# GEM_HV_channel.net
KiCad netlist of a schematic drawn in Altium Designer
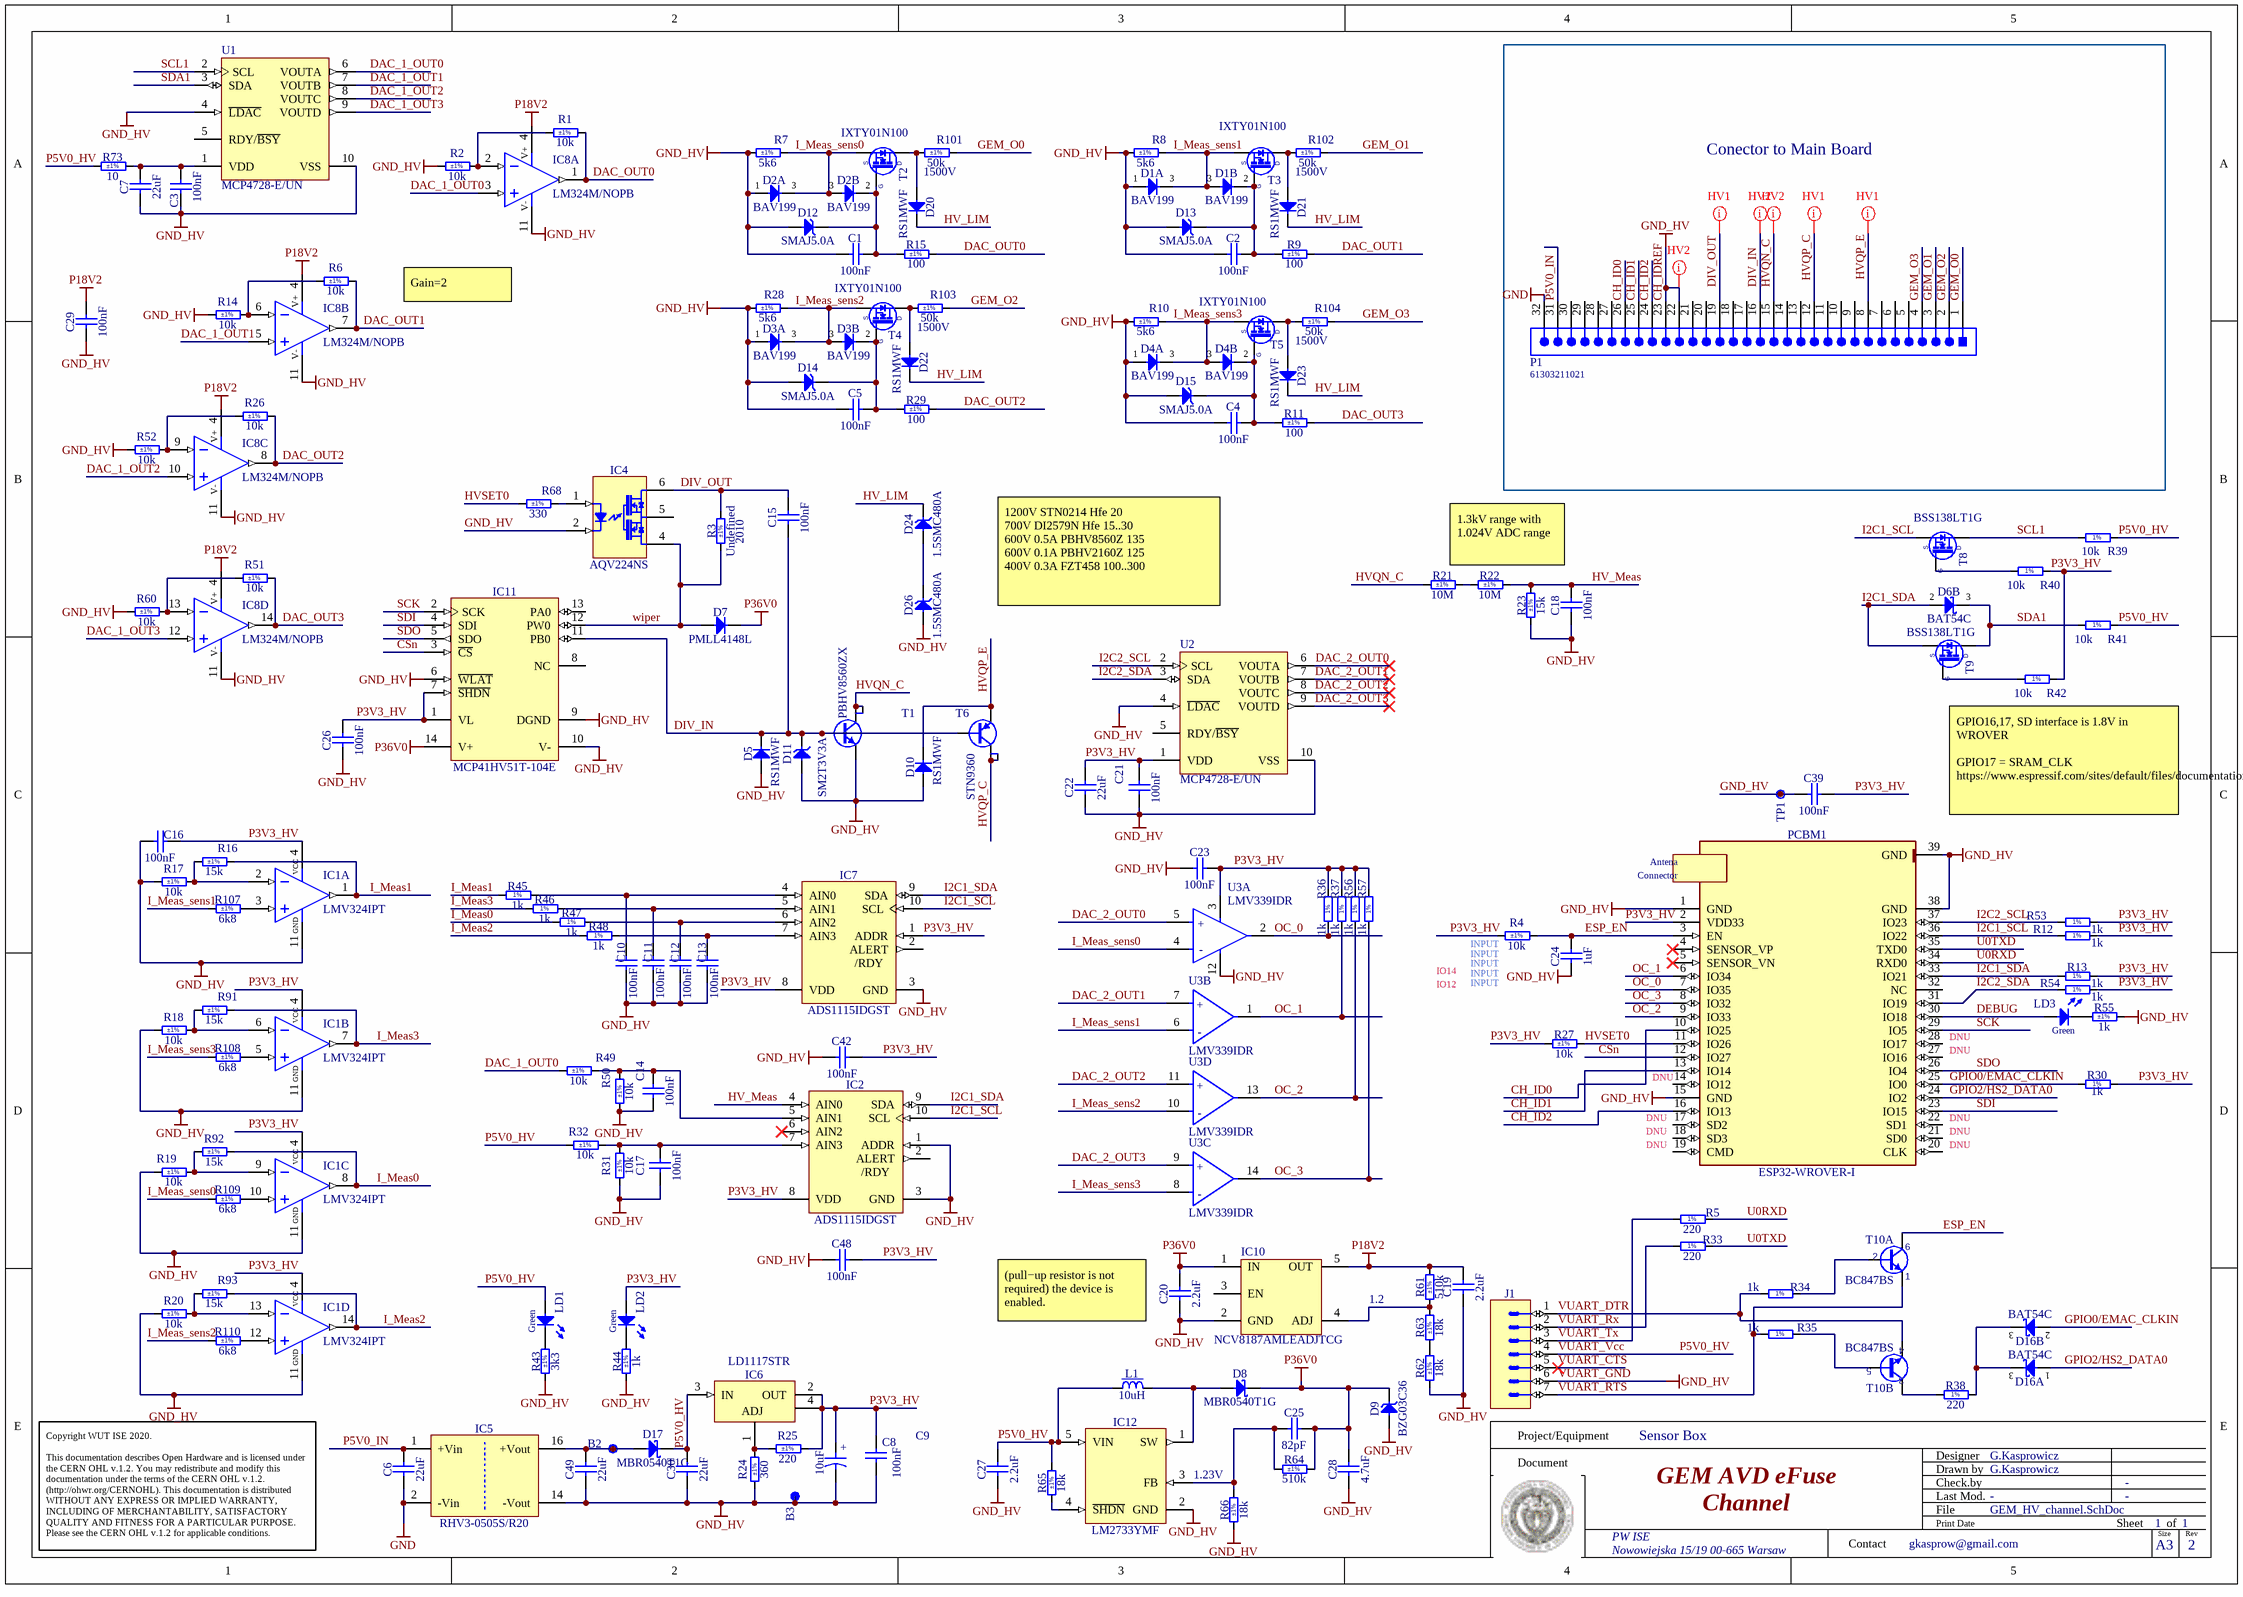
[diagram p0: GEM_HV_channel.SchDoc]

(export (version "E")
  (design (tool "Eeschema 10.0.6"))
  (components
    (comp (ref "B2")
      (value "SMD Pad")
      (footprint "C100")
      (description "Pad")
      (fields (field (name "PART NUMBER") "SMD_PAD_D1MM") (field (name "AUTHOR") "CERN DEM JLC"))
      (libsource (lib "Eletro-mechanical") (part "Single SMD Pad (Round)"))
    )
    (comp (ref "B3")
      (value "SMD Pad")
      (footprint "C100")
      (description "Pad")
      (fields (field (name "PART NUMBER") "SMD_PAD_D1MM") (field (name "AUTHOR") "CERN DEM JLC"))
      (libsource (lib "Eletro-mechanical") (part "Single SMD Pad (Round)"))
    )
    (comp (ref "C1")
      (value "100nF")
      (footprint "CAPC1608X87N")
      (description "Non-polarised capacitor")
      (fields
        (field (name "PART NUMBER") "CC0603_100NF_50V_10%_X5R")
        (field (name "VOLTAGE") "50V")
        (field (name "AUTHOR") "CERN DEM MR")
      )
      (libsource (lib "Capacitors") (part "Capacitor - non polarized"))
    )
    (comp (ref "C2")
      (value "100nF")
      (footprint "CAPC1608X87N")
      (description "Non-polarised capacitor")
      (fields
        (field (name "PART NUMBER") "CC0603_100NF_50V_10%_X5R")
        (field (name "VOLTAGE") "50V")
        (field (name "AUTHOR") "CERN DEM MR")
      )
      (libsource (lib "Capacitors") (part "Capacitor - non polarized"))
    )
    (comp (ref "C3")
      (value "100nF")
      (footprint "CAPC1608X87N")
      (description "Non-polarised capacitor")
      (fields
        (field (name "PART NUMBER") "CC0603_100NF_50V_10%_X5R")
        (field (name "VOLTAGE") "50V")
        (field (name "AUTHOR") "CERN DEM MR")
      )
      (libsource (lib "Capacitors") (part "Capacitor - non polarized"))
    )
    (comp (ref "C4")
      (value "100nF")
      (footprint "CAPC1608X87N")
      (description "Non-polarised capacitor")
      (fields
        (field (name "PART NUMBER") "CC0603_100NF_50V_10%_X5R")
        (field (name "VOLTAGE") "50V")
        (field (name "AUTHOR") "CERN DEM MR")
      )
      (libsource (lib "Capacitors") (part "Capacitor - non polarized"))
    )
    (comp (ref "C5")
      (value "100nF")
      (footprint "CAPC1608X87N")
      (description "Non-polarised capacitor")
      (fields
        (field (name "PART NUMBER") "CC0603_100NF_50V_10%_X5R")
        (field (name "VOLTAGE") "50V")
        (field (name "AUTHOR") "CERN DEM MR")
      )
      (libsource (lib "Capacitors") (part "Capacitor - non polarized"))
    )
    (comp (ref "C6")
      (value "22uF")
      (footprint "CAPC2012X145N")
      (description "Non-polarised capacitor")
      (fields
        (field (name "PART NUMBER") "CC0805_22UF_25V_20%_X5R")
        (field (name "VOLTAGE") "25V")
        (field (name "AUTHOR") "CERN DEM WB")
      )
      (libsource (lib "Capacitors") (part "Capacitor - non polarized"))
    )
    (comp (ref "C7")
      (value "22uF")
      (footprint "CAPC2012X145N")
      (description "Non-polarised capacitor")
      (fields
        (field (name "PART NUMBER") "CC0805_22UF_25V_20%_X5R")
        (field (name "VOLTAGE") "25V")
        (field (name "AUTHOR") "CERN DEM WB")
      )
      (libsource (lib "Capacitors") (part "Capacitor - non polarized"))
    )
    (comp (ref "C8")
      (value "10uF")
      (footprint "CAPAE430X540N")
      (description "Polarised capacitor")
      (fields
        (field (name "PART NUMBER") "CAE430-540_10UF_16V_20%")
        (field (name "VOLTAGE") "16V")
        (field (name "AUTHOR") "CERN DEM JLC")
      )
      (libsource (lib "Capacitors") (part "Capacitor - polarized"))
    )
    (comp (ref "C9")
      (value "100nF")
      (footprint "CAPC1608X87N")
      (description "Non-polarised capacitor")
      (fields
        (field (name "PART NUMBER") "CC0603_100NF_50V_10%_X5R")
        (field (name "VOLTAGE") "50V")
        (field (name "AUTHOR") "CERN DEM MR")
      )
      (libsource (lib "Capacitors") (part "Capacitor - non polarized"))
    )
    (comp (ref "C10")
      (value "100nF")
      (footprint "CAPC1608X87N")
      (description "Non-polarised capacitor")
      (fields
        (field (name "PART NUMBER") "CC0603_100NF_50V_10%_X5R")
        (field (name "VOLTAGE") "50V")
        (field (name "AUTHOR") "CERN DEM MR")
      )
      (libsource (lib "Capacitors") (part "Capacitor - non polarized"))
    )
    (comp (ref "C11")
      (value "100nF")
      (footprint "CAPC1608X87N")
      (description "Non-polarised capacitor")
      (fields
        (field (name "PART NUMBER") "CC0603_100NF_50V_10%_X5R")
        (field (name "VOLTAGE") "50V")
        (field (name "AUTHOR") "CERN DEM MR")
      )
      (libsource (lib "Capacitors") (part "Capacitor - non polarized"))
    )
    (comp (ref "C12")
      (value "100nF")
      (footprint "CAPC1608X87N")
      (description "Non-polarised capacitor")
      (fields
        (field (name "PART NUMBER") "CC0603_100NF_50V_10%_X5R")
        (field (name "VOLTAGE") "50V")
        (field (name "AUTHOR") "CERN DEM MR")
      )
      (libsource (lib "Capacitors") (part "Capacitor - non polarized"))
    )
    (comp (ref "C13")
      (value "100nF")
      (footprint "CAPC1608X87N")
      (description "Non-polarised capacitor")
      (fields
        (field (name "PART NUMBER") "CC0603_100NF_50V_10%_X5R")
        (field (name "VOLTAGE") "50V")
        (field (name "AUTHOR") "CERN DEM MR")
      )
      (libsource (lib "Capacitors") (part "Capacitor - non polarized"))
    )
    (comp (ref "C14")
      (value "100nF")
      (footprint "CAPC1608X87N")
      (description "Non-polarised capacitor")
      (fields
        (field (name "PART NUMBER") "CC0603_100NF_50V_10%_X5R")
        (field (name "VOLTAGE") "50V")
        (field (name "AUTHOR") "CERN DEM MR")
      )
      (libsource (lib "Capacitors") (part "Capacitor - non polarized"))
    )
    (comp (ref "C15")
      (value "100nF")
      (footprint "CAPC4532X185N")
      (description "Non-polarised capacitor")
      (fields
        (field (name "PART NUMBER") "CC1812_100NF_1000V_10%_X7R_KEMET_HV FT-CAP")
        (field (name "VOLTAGE") "1000V")
        (field (name "AUTHOR") "CERN DEM MR")
      )
      (libsource (lib "Capacitors") (part "Capacitor - non polarized"))
    )
    (comp (ref "C16")
      (value "100nF")
      (footprint "CAPC1608X87N")
      (description "Non-polarised capacitor")
      (fields
        (field (name "PART NUMBER") "CC0603_100NF_50V_10%_X5R")
        (field (name "VOLTAGE") "50V")
        (field (name "AUTHOR") "CERN DEM MR")
      )
      (libsource (lib "Capacitors") (part "Capacitor - non polarized"))
    )
    (comp (ref "C17")
      (value "100nF")
      (footprint "CAPC1608X87N")
      (description "Non-polarised capacitor")
      (fields
        (field (name "PART NUMBER") "CC0603_100NF_50V_10%_X5R")
        (field (name "VOLTAGE") "50V")
        (field (name "AUTHOR") "CERN DEM MR")
      )
      (libsource (lib "Capacitors") (part "Capacitor - non polarized"))
    )
    (comp (ref "C18")
      (value "100nF")
      (footprint "CAPC1608X87N")
      (description "Non-polarised capacitor")
      (fields
        (field (name "PART NUMBER") "CC0603_100NF_50V_10%_X5R")
        (field (name "VOLTAGE") "50V")
        (field (name "AUTHOR") "CERN DEM MR")
      )
      (libsource (lib "Capacitors") (part "Capacitor - non polarized"))
    )
    (comp (ref "C19")
      (value "2.2uF")
      (footprint "CAPC1608X87N")
      (description "Non-polarised capacitor")
      (fields
        (field (name "PART NUMBER") "CC0603_2.2UF_16V_10%_X5R")
        (field (name "VOLTAGE") "16V")
        (field (name "AUTHOR") "CERN DEM JLC")
      )
      (libsource (lib "Capacitors") (part "Capacitor - non polarized"))
    )
    (comp (ref "C20")
      (value "2.2uF")
      (footprint "CAPC1608X87N")
      (description "Non-polarised capacitor")
      (fields
        (field (name "PART NUMBER") "CC0603_2.2UF_16V_10%_X5R")
        (field (name "VOLTAGE") "16V")
        (field (name "AUTHOR") "CERN DEM JLC")
      )
      (libsource (lib "Capacitors") (part "Capacitor - non polarized"))
    )
    (comp (ref "C21")
      (value "100nF")
      (footprint "CAPC1608X87N")
      (description "Non-polarised capacitor")
      (fields
        (field (name "PART NUMBER") "CC0603_100NF_50V_10%_X5R")
        (field (name "VOLTAGE") "50V")
        (field (name "AUTHOR") "CERN DEM MR")
      )
      (libsource (lib "Capacitors") (part "Capacitor - non polarized"))
    )
    (comp (ref "C22")
      (value "22uF")
      (footprint "CAPC2012X145N")
      (description "Non-polarised capacitor")
      (fields
        (field (name "PART NUMBER") "CC0805_22UF_25V_20%_X5R")
        (field (name "VOLTAGE") "25V")
        (field (name "AUTHOR") "CERN DEM WB")
      )
      (libsource (lib "Capacitors") (part "Capacitor - non polarized"))
    )
    (comp (ref "C23")
      (value "100nF")
      (footprint "CAPC1608X87N")
      (description "Non-polarised capacitor")
      (fields
        (field (name "PART NUMBER") "CC0603_100NF_50V_10%_X5R")
        (field (name "VOLTAGE") "50V")
        (field (name "AUTHOR") "CERN DEM MR")
      )
      (libsource (lib "Capacitors") (part "Capacitor - non polarized"))
    )
    (comp (ref "C24")
      (value "1uF")
      (footprint "CAPC1608X87N")
      (description "Non-polarised capacitor")
      (fields
        (field (name "PART NUMBER") "CC0603_1UF_25V_10%_X7R")
        (field (name "VOLTAGE") "25V")
        (field (name "AUTHOR") "CERN DEM JLC")
      )
      (libsource (lib "Capacitors") (part "Capacitor - non polarized"))
    )
    (comp (ref "C25")
      (value "82pF")
      (footprint "CAPC1608X87N")
      (description "Non-polarised capacitor")
      (fields
        (field (name "PART NUMBER") "CC0603_82PF_50V_5%_NP0")
        (field (name "VOLTAGE") "50V")
        (field (name "AUTHOR") "CERN DEM JLC")
      )
      (libsource (lib "Capacitors") (part "Capacitor - non polarized"))
    )
    (comp (ref "C26")
      (value "100nF")
      (footprint "CAPC1608X87N")
      (description "Non-polarised capacitor")
      (fields
        (field (name "PART NUMBER") "CC0603_100NF_50V_10%_X5R")
        (field (name "VOLTAGE") "50V")
        (field (name "AUTHOR") "CERN DEM MR")
      )
      (libsource (lib "Capacitors") (part "Capacitor - non polarized"))
    )
    (comp (ref "C27")
      (value "2.2uF")
      (footprint "CAPC1608X87N")
      (description "Non-polarised capacitor")
      (fields
        (field (name "PART NUMBER") "CC0603_2.2UF_16V_10%_X5R")
        (field (name "VOLTAGE") "16V")
        (field (name "AUTHOR") "CERN DEM JLC")
      )
      (libsource (lib "Capacitors") (part "Capacitor - non polarized"))
    )
    (comp (ref "C28")
      (value "4.7uF")
      (footprint "CAPC3225X270N")
      (description "Non-polarised capacitor")
      (fields
        (field (name "PART NUMBER") "CC1210_4.7UF_50V_10%_X7R")
        (field (name "VOLTAGE") "50V")
        (field (name "AUTHOR") "CERN DEM JLC")
      )
      (libsource (lib "Capacitors") (part "Capacitor - non polarized"))
    )
    (comp (ref "C29")
      (value "100nF")
      (footprint "CAPC1608X87N")
      (description "Non-polarised capacitor")
      (fields
        (field (name "PART NUMBER") "CC0603_100NF_50V_10%_X5R")
        (field (name "VOLTAGE") "50V")
        (field (name "AUTHOR") "CERN DEM MR")
      )
      (libsource (lib "Capacitors") (part "Capacitor - non polarized"))
    )
    (comp (ref "C30")
      (value "22uF")
      (footprint "CAPC2012X145N")
      (description "Non-polarised capacitor")
      (fields
        (field (name "PART NUMBER") "CC0805_22UF_25V_20%_X5R")
        (field (name "VOLTAGE") "25V")
        (field (name "AUTHOR") "CERN DEM WB")
      )
      (libsource (lib "Capacitors") (part "Capacitor - non polarized"))
    )
    (comp (ref "C39")
      (value "100nF")
      (footprint "CAPC1608X87N")
      (description "Non-polarised capacitor")
      (fields
        (field (name "PART NUMBER") "CC0603_100NF_50V_10%_X5R")
        (field (name "VOLTAGE") "50V")
        (field (name "AUTHOR") "CERN DEM MR")
      )
      (libsource (lib "Capacitors") (part "Capacitor - non polarized"))
    )
    (comp (ref "C42")
      (value "100nF")
      (footprint "CAPC1608X87N")
      (description "Non-polarised capacitor")
      (fields
        (field (name "PART NUMBER") "CC0603_100NF_50V_10%_X5R")
        (field (name "VOLTAGE") "50V")
        (field (name "AUTHOR") "CERN DEM MR")
      )
      (libsource (lib "Capacitors") (part "Capacitor - non polarized"))
    )
    (comp (ref "C48")
      (value "100nF")
      (footprint "CAPC1608X87N")
      (description "Non-polarised capacitor")
      (fields
        (field (name "PART NUMBER") "CC0603_100NF_50V_10%_X5R")
        (field (name "VOLTAGE") "50V")
        (field (name "AUTHOR") "CERN DEM MR")
      )
      (libsource (lib "Capacitors") (part "Capacitor - non polarized"))
    )
    (comp (ref "C49")
      (value "22uF")
      (footprint "CAPC2012X145N")
      (description "Non-polarised capacitor")
      (fields
        (field (name "PART NUMBER") "CC0805_22UF_25V_20%_X5R")
        (field (name "VOLTAGE") "25V")
        (field (name "AUTHOR") "CERN DEM WB")
      )
      (libsource (lib "Capacitors") (part "Capacitor - non polarized"))
    )
    (comp (ref "D1")
      (value "BAV199")
      (footprint "SOT95P240X110-3N")
      (description "Serial Diode")
      (fields
        (field (name "VOLTAGE") "75V")
        (field (name "POWER") "250mW")
        (field (name "AUTHOR") "CERN DEM JMW")
      )
      (libsource (lib "ICs And Semiconductors") (part "Diode x2 A1C3_A3C2"))
    )
    (comp (ref "D2")
      (value "BAV199")
      (footprint "SOT95P240X110-3N")
      (description "Serial Diode")
      (fields
        (field (name "VOLTAGE") "75V")
        (field (name "POWER") "250mW")
        (field (name "AUTHOR") "CERN DEM JMW")
      )
      (libsource (lib "ICs And Semiconductors") (part "Diode x2 A1C3_A3C2"))
    )
    (comp (ref "D3")
      (value "BAV199")
      (footprint "SOT95P240X110-3N")
      (description "Serial Diode")
      (fields
        (field (name "VOLTAGE") "75V")
        (field (name "POWER") "250mW")
        (field (name "AUTHOR") "CERN DEM JMW")
      )
      (libsource (lib "ICs And Semiconductors") (part "Diode x2 A1C3_A3C2"))
    )
    (comp (ref "D4")
      (value "BAV199")
      (footprint "SOT95P240X110-3N")
      (description "Serial Diode")
      (fields
        (field (name "VOLTAGE") "75V")
        (field (name "POWER") "250mW")
        (field (name "AUTHOR") "CERN DEM JMW")
      )
      (libsource (lib "ICs And Semiconductors") (part "Diode x2 A1C3_A3C2"))
    )
    (comp (ref "D5")
      (value "RS1MWF")
      (footprint "SOD-123F")
      (description "Diode")
      (fields
        (field (name "VOLTAGE") "1000V")
        (field (name "POWER") "1A")
        (field (name "AUTHOR") "CERN DEM HF")
      )
      (libsource (lib "ICs And Semiconductors") (part "Diode"))
    )
    (comp (ref "D6")
      (value "BAT54C")
      (footprint "SOT95P240X130-3N")
      (description "Dual Common Cathode Schottky Diodes")
      (fields
        (field (name "VOLTAGE") "30V")
        (field (name "POWER") "200mA")
        (field (name "AUTHOR") "CERN DEM JLC")
      )
      (libsource (lib "ICs And Semiconductors") (part "Diode Schottky x2 A1C3_A2C3"))
    )
    (comp (ref "D7")
      (value "PMLL4148L")
      (footprint "DIOMELF3515N")
      (description "Diode")
      (fields
        (field (name "VOLTAGE") "75V")
        (field (name "POWER") "200mA")
        (field (name "AUTHOR") "CERN DEM JLC")
      )
      (libsource (lib "ICs And Semiconductors") (part "Diode"))
    )
    (comp (ref "D8")
      (value "MBR0540T1G")
      (footprint "SOD3716X135N")
      (description "Schottky Diode")
      (fields
        (field (name "VOLTAGE") "40V")
        (field (name "POWER") "500mA")
        (field (name "AUTHOR") "CERN DEM JLC")
      )
      (libsource (lib "ICs And Semiconductors") (part "Diode Schottky"))
    )
    (comp (ref "D9")
      (value "BZG03C36")
      (footprint "DIOM5326X230N")
      (description "Zener Diode")
      (fields
        (field (name "VOLTAGE") "36V")
        (field (name "POWER") "1.25W")
        (field (name "AUTHOR") "CERN DEM JLC")
      )
      (libsource (lib "ICs And Semiconductors") (part "Diode Zener"))
    )
    (comp (ref "D10")
      (value "RS1MWF")
      (footprint "SOD-123F")
      (description "Diode")
      (fields
        (field (name "VOLTAGE") "1000V")
        (field (name "POWER") "1A")
        (field (name "AUTHOR") "CERN DEM HF")
      )
      (libsource (lib "ICs And Semiconductors") (part "Diode"))
    )
    (comp (ref "D11")
      (value "SM2T3V3A")
      (footprint "DO-216AA")
      (description "Transient Voltage Suppressor Diode (Uni-Directional)")
      (fields
        (field (name "VOLTAGE") "3V3")
        (field (name "POWER") "200W")
        (field (name "AUTHOR") "CERN DEM BR")
      )
      (libsource (lib "ICs And Semiconductors") (part "Diode TVS Uni-Directional"))
    )
    (comp (ref "D12")
      (value "SMAJ5.0A")
      (footprint "DIOM5226X262N")
      (description "Transient Voltage Suppressor Diode (Uni-Directional)")
      (fields
        (field (name "VOLTAGE") "5V")
        (field (name "POWER") "400W")
        (field (name "AUTHOR") "CERN DEM MR")
      )
      (libsource (lib "ICs And Semiconductors") (part "Diode TVS Uni-Directional"))
    )
    (comp (ref "D13")
      (value "SMAJ5.0A")
      (footprint "DIOM5226X262N")
      (description "Transient Voltage Suppressor Diode (Uni-Directional)")
      (fields
        (field (name "VOLTAGE") "5V")
        (field (name "POWER") "400W")
        (field (name "AUTHOR") "CERN DEM MR")
      )
      (libsource (lib "ICs And Semiconductors") (part "Diode TVS Uni-Directional"))
    )
    (comp (ref "D14")
      (value "SMAJ5.0A")
      (footprint "DIOM5226X262N")
      (description "Transient Voltage Suppressor Diode (Uni-Directional)")
      (fields
        (field (name "VOLTAGE") "5V")
        (field (name "POWER") "400W")
        (field (name "AUTHOR") "CERN DEM MR")
      )
      (libsource (lib "ICs And Semiconductors") (part "Diode TVS Uni-Directional"))
    )
    (comp (ref "D15")
      (value "SMAJ5.0A")
      (footprint "DIOM5226X262N")
      (description "Transient Voltage Suppressor Diode (Uni-Directional)")
      (fields
        (field (name "VOLTAGE") "5V")
        (field (name "POWER") "400W")
        (field (name "AUTHOR") "CERN DEM MR")
      )
      (libsource (lib "ICs And Semiconductors") (part "Diode TVS Uni-Directional"))
    )
    (comp (ref "D16")
      (value "BAT54C")
      (footprint "SOT95P240X130-3N")
      (description "Dual Common Cathode Schottky Diodes")
      (fields
        (field (name "VOLTAGE") "30V")
        (field (name "POWER") "200mA")
        (field (name "AUTHOR") "CERN DEM JLC")
      )
      (libsource (lib "ICs And Semiconductors") (part "Diode Schottky x2 A1C3_A2C3"))
    )
    (comp (ref "D17")
      (value "MBR0540T1G")
      (footprint "SOD3716X135N")
      (description "Schottky Diode")
      (fields
        (field (name "VOLTAGE") "40V")
        (field (name "POWER") "500mA")
        (field (name "AUTHOR") "CERN DEM JLC")
      )
      (libsource (lib "ICs And Semiconductors") (part "Diode Schottky"))
    )
    (comp (ref "D20")
      (value "RS1MWF")
      (footprint "SOD-123F")
      (description "Diode")
      (fields
        (field (name "VOLTAGE") "1000V")
        (field (name "POWER") "1A")
        (field (name "AUTHOR") "CERN DEM HF")
      )
      (libsource (lib "ICs And Semiconductors") (part "Diode"))
    )
    (comp (ref "D21")
      (value "RS1MWF")
      (footprint "SOD-123F")
      (description "Diode")
      (fields
        (field (name "VOLTAGE") "1000V")
        (field (name "POWER") "1A")
        (field (name "AUTHOR") "CERN DEM HF")
      )
      (libsource (lib "ICs And Semiconductors") (part "Diode"))
    )
    (comp (ref "D22")
      (value "RS1MWF")
      (footprint "SOD-123F")
      (description "Diode")
      (fields
        (field (name "VOLTAGE") "1000V")
        (field (name "POWER") "1A")
        (field (name "AUTHOR") "CERN DEM HF")
      )
      (libsource (lib "ICs And Semiconductors") (part "Diode"))
    )
    (comp (ref "D23")
      (value "RS1MWF")
      (footprint "SOD-123F")
      (description "Diode")
      (fields
        (field (name "VOLTAGE") "1000V")
        (field (name "POWER") "1A")
        (field (name "AUTHOR") "CERN DEM HF")
      )
      (libsource (lib "ICs And Semiconductors") (part "Diode"))
    )
    (comp (ref "D24")
      (value "1.5SMC480A")
      (footprint "DIOM7959X262N")
      (description "Transient Voltage Suppressor Diode (Uni-Directional)")
      (fields
        (field (name "VOLTAGE") "480V")
        (field (name "POWER") "1500W")
        (field (name "AUTHOR") "CERN DEM HF")
      )
      (libsource (lib "ICs And Semiconductors") (part "Diode TVS Uni-Directional"))
    )
    (comp (ref "D26")
      (value "1.5SMC480A")
      (footprint "DIOM7959X262N")
      (description "Transient Voltage Suppressor Diode (Uni-Directional)")
      (fields
        (field (name "VOLTAGE") "480V")
        (field (name "POWER") "1500W")
        (field (name "AUTHOR") "CERN DEM HF")
      )
      (libsource (lib "ICs And Semiconductors") (part "Diode TVS Uni-Directional"))
    )
    (comp (ref "IC1")
      (value "LMV324IPT")
      (footprint "SOP65P640X110-14N")
      (description "Quad Operational Amplifier")
      (fields (field (name "MANUFACTURER") "TEXAS INSTRUMENTS") (field (name "AUTHOR") "GK"))
      (libsource (lib "Amplifiers") (part "OA_LMV324_TSSOP"))
    )
    (comp (ref "IC2")
      (value "ADS1115IDGST")
      (footprint "SOP50P490X110-10N")
      (description "Ultra-Small, Low-Power, 16-Bit Analog-to-Digital Converter with Internal Reference")
      (fields
        (field (name "MANUFACTURER") "TEXAS INSTRUMENTS")
        (field (name "MANUFACTURER PART NUMBER") "ADS1115IDGS")
        (field (name "AUTHOR") "CERN DEM JLC")
      )
      (libsource (lib "ICs And Semiconductors") (part "ADS1115"))
    )
    (comp (ref "IC4")
      (value "AQV224NS")
      (footprint "PANASONIC_AQV22(SOP)")
      (description "PhotoMOS Relay 400V 40mA")
      (fields (field (name "MANUFACTURER") "PANASONIC") (field (name "AUTHOR") "GK"))
      (libsource (lib "Optoisolators") (part "OPTOMOS_AQV224NS"))
    )
    (comp (ref "IC5")
      (value "RHV3-0505S/R20")
      (footprint "DCDC_RECOM_RHV3_Single")
      (description "RECOM, RP Series, Single Output DCDC Converter")
      (fields (field (name "MANUFACTURER") "RECOM") (field (name "AUTHOR") "CERN DEM HF"))
      (libsource (lib "ICs And Semiconductors") (part "DCDC_RECOM_RHV3_Single"))
    )
    (comp (ref "IC6")
      (value "LD1117STR")
      (footprint "SOT230P700X180-4N")
      (description "3-Terminal Regulator 1=Adj 2=OUT 3=IN 4=OUT")
      (fields (field (name "MANUFACTURER") "ST MICROELECTRONICS") (field (name "AUTHOR") "CERN DEM MR"))
      (libsource (lib "ICs And Semiconductors") (part "REG3+1 1ADJ-2OUT-3IN+4OUT"))
    )
    (comp (ref "IC7")
      (value "ADS1115IDGST")
      (footprint "SOP50P490X110-10N")
      (description "Ultra-Small, Low-Power, 16-Bit Analog-to-Digital Converter with Internal Reference")
      (fields
        (field (name "MANUFACTURER") "TEXAS INSTRUMENTS")
        (field (name "MANUFACTURER PART NUMBER") "ADS1115IDGS")
        (field (name "AUTHOR") "CERN DEM JLC")
      )
      (libsource (lib "ICs And Semiconductors") (part "ADS1115"))
    )
    (comp (ref "IC8")
      (value "LM324M/NOPB")
      (footprint "SOIC127P600X175-14N")
      (description "Quad Operational Amplifier")
      (fields
        (field (name "MANUFACTURER") "FAIRCHILD SEMICONDUCTOR")
        (field (name "MANUFACTURER PART NUMBER") "LM324M")
        (field (name "AUTHOR") "CERN DEM JLC")
      )
      (libsource (lib "ICs And Semiconductors") (part "Operational Amplifier x4 Type1"))
    )
    (comp (ref "IC10")
      (value "NCV8187AMLEADJTCG")
      (footprint "SOT23-5")
      (description "LDO Regulator, 150 mA,\r\n38V")
      (fields
        (field (name "MANUFACTURER") "Onsemi")
        (field (name "MANUFACTURER PART NUMBER") "NCV8730ASNADJT1G")
      )
      (libsource (lib "templib") (part "NCV8730ASNADJT1G"))
    )
    (comp (ref "IC11")
      (value "MCP41HV51T-104E")
      (footprint "SOP65P640X120-14N")
      (description "8-Bit Single, +36V (±18V) Digital POT with SPI /100kOhm (-40°C to 125°C)")
      (fields (field (name "MANUFACTURER") "MICROCHIP TECHNOLOGY") (field (name "AUTHOR") "GK"))
      (libsource (lib "ADC_DAC") (part "MCP41HV51T-104E"))
    )
    (comp (ref "IC12")
      (value "LM2733YMF")
      (footprint "SOT95P284X122-5N")
      (description "0.6/1.6 MHz Boost Converters With 40V Internal FET Switch in SOT-23")
      (fields (field (name "MANUFACTURER") "TEXAS INSTRUMENTS") (field (name "AUTHOR") "GK"))
      (libsource (lib "Regulators_SMPS") (part "PM_LM2733YMF"))
    )
    (comp (ref "J1")
      (value "Header 7")
      (footprint "SAMTEC_TSW-107-07-L-S-LL")
      (description "Connector 7 Male")
      (fields
        (field (name "PART NUMBER") "SAMTEC_TSW-107-07-L-S-LL")
        (field (name "MANUFACTURER") "SAMTEC")
        (field (name "AUTHOR") "CERN DEM MR")
      )
      (libsource (lib "Connectors") (part "Connector 7 Male"))
    )
    (comp (ref "L1")
      (value "10uH")
      (footprint "IND_TDK_VLCF5020-1")
      (description "Inductor With Core")
      (fields
        (field (name "PART NUMBER") "IND_10UH_20%_TDK_VLCF5020-1")
        (field (name "POWER") "1.5A")
        (field (name "AUTHOR") "CERN DEM JLC")
      )
      (libsource (lib "Inductors & Transformers") (part "Inductor With Magnetic core"))
    )
    (comp (ref "LD1")
      (value "Green")
      (footprint "LED_KINGBRIGHT_KP-1608CGCK")
      (description "LED Green 1C 2A")
      (fields
        (field (name "PART NUMBER") "LED_KINGBRIGHT_KP-1608CGCK")
        (field (name "MANUFACTURER") "KINGBRIGHT")
        (field (name "AUTHOR") "CERN DEM HF")
      )
      (libsource (lib "ICs And Semiconductors") (part "LED Green 1C 2A"))
    )
    (comp (ref "LD2")
      (value "Green")
      (footprint "LED_KINGBRIGHT_KP-1608CGCK")
      (description "LED Green 1C 2A")
      (fields
        (field (name "PART NUMBER") "LED_KINGBRIGHT_KP-1608CGCK")
        (field (name "MANUFACTURER") "KINGBRIGHT")
        (field (name "AUTHOR") "CERN DEM HF")
      )
      (libsource (lib "ICs And Semiconductors") (part "LED Green 1C 2A"))
    )
    (comp (ref "LD3")
      (value "Green")
      (footprint "LED_KINGBRIGHT_KP-1608CGCK")
      (description "LED Green 1C 2A")
      (fields
        (field (name "PART NUMBER") "LED_KINGBRIGHT_KP-1608CGCK")
        (field (name "MANUFACTURER") "KINGBRIGHT")
        (field (name "AUTHOR") "CERN DEM HF")
      )
      (libsource (lib "ICs And Semiconductors") (part "LED Green 1C 2A"))
    )
    (comp (ref "P1")
      (value "61303211021")
      (footprint "61303211021")
      (description "WR-PHD Pin Header, THT, pitch 2.54mm, Single Row, Angled, 32p")
      (fields (field (name "MANUFACTURER") "Wurth Elektronik"))
      (libsource (lib "Altium_WR-PHD (rev22a)") (part "61303211021"))
    )
    (comp (ref "PCBM1")
      (value "ESP32-WROVER-I")
      (footprint "PCBM_ESP32-WROVER-I")
      (description "Generic WiFi-BT-BLE MCU Module")
      (fields
        (field (name "PART NUMBER") "PCBM_ESP32-WROVER-I")
        (field (name "MANUFACTURER") "ESPRESSIF")
        (field (name "AUTHOR") "CERN DEM JLC")
      )
      (libsource (lib "ICs And Semiconductors") (part "PCBM_ESP32-WROVER-I"))
    )
    (comp (ref "R1")
      (value "10k")
      (footprint "RESC1608X55N")
      (description "Resistor - 1%")
      (fields
        (field (name "TOLERANCE") "±1%")
        (field (name "PART NUMBER") "R0603_10K_1%_0.1W_100PPM")
        (field (name "POWER") "0.1W")
        (field (name "AUTHOR") "CERN DEM JLC")
      )
      (libsource (lib "Resistors") (part "Resistor - 1%"))
    )
    (comp (ref "R2")
      (value "10k")
      (footprint "RESC1608X55N")
      (description "Resistor - 1%")
      (fields
        (field (name "TOLERANCE") "±1%")
        (field (name "PART NUMBER") "R0603_10K_1%_0.1W_100PPM")
        (field (name "POWER") "0.1W")
        (field (name "AUTHOR") "CERN DEM JLC")
      )
      (libsource (lib "Resistors") (part "Resistor - 1%"))
    )
    (comp (ref "R3")
      (value "Undefined")
      (footprint "RES_VISHAY_CRHV2010A")
      (description "Resistor - 1%")
      (fields
        (field (name "TOLERANCE") "±1%")
        (field (name "POWER") "0.5W")
        (field (name "MANUFACTURER") "VISHAY TECHNO")
        (field (name "CASE") "2010")
        (field (name "AUTHOR") "CERN DEM JLC")
      )
      (libsource (lib "Resistors") (part "Resistor - 1%"))
    )
    (comp (ref "R4")
      (value "10k")
      (footprint "RESC1608X55N")
      (description "Resistor - 1%")
      (fields
        (field (name "TOLERANCE") "±1%")
        (field (name "PART NUMBER") "R0603_10K_1%_0.1W_100PPM")
        (field (name "POWER") "0.1W")
        (field (name "AUTHOR") "CERN DEM JLC")
      )
      (libsource (lib "Resistors") (part "Resistor - 1%"))
    )
    (comp (ref "R5")
      (value "220")
      (footprint "RESC1005X40N")
      (description "Resistor - 1%")
      (fields
        (field (name "PART NUMBER") "R0402_220R_1%_0.0625W_100PPM")
        (field (name "POWER") "0.0625W")
        (field (name "AUTHOR") "CERN DEM JLC")
      )
      (libsource (lib "") (part "Resistor - 1%_1"))
    )
    (comp (ref "R6")
      (value "10k")
      (footprint "RESC1608X55N")
      (description "Resistor - 1%")
      (fields
        (field (name "TOLERANCE") "±1%")
        (field (name "PART NUMBER") "R0603_10K_1%_0.1W_100PPM")
        (field (name "POWER") "0.1W")
        (field (name "AUTHOR") "CERN DEM JLC")
      )
      (libsource (lib "Resistors") (part "Resistor - 1%"))
    )
    (comp (ref "R7")
      (value "5k6")
      (footprint "RESC2012X60N")
      (description "Resistor - 1%")
      (fields
        (field (name "TOLERANCE") "±1%")
        (field (name "PART NUMBER") "R0805_5K6_1%_0.125W_100PPM")
        (field (name "POWER") "0.125W")
        (field (name "AUTHOR") "CERN DEM JLC")
      )
      (libsource (lib "Resistors") (part "Resistor - 1%"))
    )
    (comp (ref "R8")
      (value "5k6")
      (footprint "RESC2012X60N")
      (description "Resistor - 1%")
      (fields
        (field (name "TOLERANCE") "±1%")
        (field (name "PART NUMBER") "R0805_5K6_1%_0.125W_100PPM")
        (field (name "POWER") "0.125W")
        (field (name "AUTHOR") "CERN DEM JLC")
      )
      (libsource (lib "Resistors") (part "Resistor - 1%"))
    )
    (comp (ref "R9")
      (value "100")
      (footprint "RESC1608X55N")
      (description "Resistor - 1%")
      (fields
        (field (name "TOLERANCE") "±1%")
        (field (name "PART NUMBER") "R0603_100R_1%_0.1W_100PPM")
        (field (name "POWER") "0.1W")
        (field (name "AUTHOR") "CERN DEM JLC")
      )
      (libsource (lib "Resistors") (part "Resistor - 1%"))
    )
    (comp (ref "R10")
      (value "5k6")
      (footprint "RESC2012X60N")
      (description "Resistor - 1%")
      (fields
        (field (name "TOLERANCE") "±1%")
        (field (name "PART NUMBER") "R0805_5K6_1%_0.125W_100PPM")
        (field (name "POWER") "0.125W")
        (field (name "AUTHOR") "CERN DEM JLC")
      )
      (libsource (lib "Resistors") (part "Resistor - 1%"))
    )
    (comp (ref "R11")
      (value "100")
      (footprint "RESC1608X55N")
      (description "Resistor - 1%")
      (fields
        (field (name "TOLERANCE") "±1%")
        (field (name "PART NUMBER") "R0603_100R_1%_0.1W_100PPM")
        (field (name "POWER") "0.1W")
        (field (name "AUTHOR") "CERN DEM JLC")
      )
      (libsource (lib "Resistors") (part "Resistor - 1%"))
    )
    (comp (ref "R12")
      (value "1k")
      (footprint "RESC1005X40N")
      (description "Resistor - 1%")
      (fields
        (field (name "PART NUMBER") "R0402_1K_1%_0.0625W_100PPM")
        (field (name "POWER") "0.0625W")
        (field (name "AUTHOR") "CERN DEM JLC")
      )
      (libsource (lib "") (part "Resistor - 1%_1"))
    )
    (comp (ref "R13")
      (value "1k")
      (footprint "RESC1005X40N")
      (description "Resistor - 1%")
      (fields
        (field (name "PART NUMBER") "R0402_1K_1%_0.0625W_100PPM")
        (field (name "POWER") "0.0625W")
        (field (name "AUTHOR") "CERN DEM JLC")
      )
      (libsource (lib "") (part "Resistor - 1%_1"))
    )
    (comp (ref "R14")
      (value "10k")
      (footprint "RESC1608X55N")
      (description "Resistor - 1%")
      (fields
        (field (name "TOLERANCE") "±1%")
        (field (name "PART NUMBER") "R0603_10K_1%_0.1W_100PPM")
        (field (name "POWER") "0.1W")
        (field (name "AUTHOR") "CERN DEM JLC")
      )
      (libsource (lib "Resistors") (part "Resistor - 1%"))
    )
    (comp (ref "R15")
      (value "100")
      (footprint "RESC1608X55N")
      (description "Resistor - 1%")
      (fields
        (field (name "TOLERANCE") "±1%")
        (field (name "PART NUMBER") "R0603_100R_1%_0.1W_100PPM")
        (field (name "POWER") "0.1W")
        (field (name "AUTHOR") "CERN DEM JLC")
      )
      (libsource (lib "Resistors") (part "Resistor - 1%"))
    )
    (comp (ref "R16")
      (value "15k")
      (footprint "RESC1608X55N")
      (description "Resistor - 1%")
      (fields
        (field (name "TOLERANCE") "±1%")
        (field (name "PART NUMBER") "R0603_15K_1%_0.1W_100PPM")
        (field (name "POWER") "0.1W")
        (field (name "AUTHOR") "CERN DEM JMW")
      )
      (libsource (lib "Resistors") (part "Resistor - 1%"))
    )
    (comp (ref "R17")
      (value "10k")
      (footprint "RESC1608X55N")
      (description "Resistor - 1%")
      (fields
        (field (name "TOLERANCE") "±1%")
        (field (name "PART NUMBER") "R0603_10K_1%_0.1W_100PPM")
        (field (name "POWER") "0.1W")
        (field (name "AUTHOR") "CERN DEM JLC")
      )
      (libsource (lib "Resistors") (part "Resistor - 1%"))
    )
    (comp (ref "R18")
      (value "10k")
      (footprint "RESC1608X55N")
      (description "Resistor - 1%")
      (fields
        (field (name "TOLERANCE") "±1%")
        (field (name "PART NUMBER") "R0603_10K_1%_0.1W_100PPM")
        (field (name "POWER") "0.1W")
        (field (name "AUTHOR") "CERN DEM JLC")
      )
      (libsource (lib "Resistors") (part "Resistor - 1%"))
    )
    (comp (ref "R19")
      (value "10k")
      (footprint "RESC1608X55N")
      (description "Resistor - 1%")
      (fields
        (field (name "TOLERANCE") "±1%")
        (field (name "PART NUMBER") "R0603_10K_1%_0.1W_100PPM")
        (field (name "POWER") "0.1W")
        (field (name "AUTHOR") "CERN DEM JLC")
      )
      (libsource (lib "Resistors") (part "Resistor - 1%"))
    )
    (comp (ref "R20")
      (value "10k")
      (footprint "RESC1608X55N")
      (description "Resistor - 1%")
      (fields
        (field (name "TOLERANCE") "±1%")
        (field (name "PART NUMBER") "R0603_10K_1%_0.1W_100PPM")
        (field (name "POWER") "0.1W")
        (field (name "AUTHOR") "CERN DEM JLC")
      )
      (libsource (lib "Resistors") (part "Resistor - 1%"))
    )
    (comp (ref "R21")
      (value "10M")
      (footprint "RESC5025X65N")
      (description "Resistor - 1%")
      (fields
        (field (name "TOLERANCE") "±1%")
        (field (name "PART NUMBER") "R2010_10M_1%_0.5W_200PPM")
        (field (name "POWER") "0.5W")
        (field (name "AUTHOR") "CERN DEM JLC")
      )
      (libsource (lib "Resistors") (part "Resistor - 1%"))
    )
    (comp (ref "R22")
      (value "10M")
      (footprint "RESC5025X65N")
      (description "Resistor - 1%")
      (fields
        (field (name "TOLERANCE") "±1%")
        (field (name "PART NUMBER") "R2010_10M_1%_0.5W_200PPM")
        (field (name "POWER") "0.5W")
        (field (name "AUTHOR") "CERN DEM JLC")
      )
      (libsource (lib "Resistors") (part "Resistor - 1%"))
    )
    (comp (ref "R23")
      (value "15k")
      (footprint "RESC1608X55N")
      (description "Resistor - 1%")
      (fields
        (field (name "TOLERANCE") "±1%")
        (field (name "PART NUMBER") "R0603_15K_1%_0.1W_100PPM")
        (field (name "POWER") "0.1W")
        (field (name "AUTHOR") "CERN DEM JMW")
      )
      (libsource (lib "Resistors") (part "Resistor - 1%"))
    )
    (comp (ref "R24")
      (value "360")
      (footprint "RESC1608X55N")
      (description "Resistor - 1%")
      (fields
        (field (name "TOLERANCE") "±1%")
        (field (name "PART NUMBER") "R0603_360R_1%_0.1W_100PPM")
        (field (name "POWER") "0.1W")
        (field (name "AUTHOR") "CERN DEM JLC")
      )
      (libsource (lib "Resistors") (part "Resistor - 1%"))
    )
    (comp (ref "R25")
      (value "220")
      (footprint "RESC1608X55N")
      (description "Resistor - 1%")
      (fields
        (field (name "TOLERANCE") "±1%")
        (field (name "PART NUMBER") "R0603_220R_1%_0.1W_100PPM")
        (field (name "POWER") "0.1W")
        (field (name "AUTHOR") "CERN DEM JLC")
      )
      (libsource (lib "Resistors") (part "Resistor - 1%"))
    )
    (comp (ref "R26")
      (value "10k")
      (footprint "RESC1608X55N")
      (description "Resistor - 1%")
      (fields
        (field (name "TOLERANCE") "±1%")
        (field (name "PART NUMBER") "R0603_10K_1%_0.1W_100PPM")
        (field (name "POWER") "0.1W")
        (field (name "AUTHOR") "CERN DEM JLC")
      )
      (libsource (lib "Resistors") (part "Resistor - 1%"))
    )
    (comp (ref "R27")
      (value "10k")
      (footprint "RESC1608X55N")
      (description "Resistor - 1%")
      (fields
        (field (name "TOLERANCE") "±1%")
        (field (name "PART NUMBER") "R0603_10K_1%_0.1W_100PPM")
        (field (name "POWER") "0.1W")
        (field (name "AUTHOR") "CERN DEM JLC")
      )
      (libsource (lib "Resistors") (part "Resistor - 1%"))
    )
    (comp (ref "R28")
      (value "5k6")
      (footprint "RESC2012X60N")
      (description "Resistor - 1%")
      (fields
        (field (name "TOLERANCE") "±1%")
        (field (name "PART NUMBER") "R0805_5K6_1%_0.125W_100PPM")
        (field (name "POWER") "0.125W")
        (field (name "AUTHOR") "CERN DEM JLC")
      )
      (libsource (lib "Resistors") (part "Resistor - 1%"))
    )
    (comp (ref "R29")
      (value "100")
      (footprint "RESC1608X55N")
      (description "Resistor - 1%")
      (fields
        (field (name "TOLERANCE") "±1%")
        (field (name "PART NUMBER") "R0603_100R_1%_0.1W_100PPM")
        (field (name "POWER") "0.1W")
        (field (name "AUTHOR") "CERN DEM JLC")
      )
      (libsource (lib "Resistors") (part "Resistor - 1%"))
    )
    (comp (ref "R30")
      (value "1k")
      (footprint "RESC1005X40N")
      (description "Resistor - 1%")
      (fields
        (field (name "PART NUMBER") "R0402_1K_1%_0.0625W_100PPM")
        (field (name "POWER") "0.0625W")
        (field (name "AUTHOR") "CERN DEM JLC")
      )
      (libsource (lib "") (part "Resistor - 1%_1"))
    )
    (comp (ref "R31")
      (value "10k")
      (footprint "RESC1608X55N")
      (description "Resistor - 1%")
      (fields
        (field (name "TOLERANCE") "±1%")
        (field (name "PART NUMBER") "R0603_10K_1%_0.1W_100PPM")
        (field (name "POWER") "0.1W")
        (field (name "AUTHOR") "CERN DEM JLC")
      )
      (libsource (lib "Resistors") (part "Resistor - 1%"))
    )
    (comp (ref "R32")
      (value "10k")
      (footprint "RESC1608X55N")
      (description "Resistor - 1%")
      (fields
        (field (name "TOLERANCE") "±1%")
        (field (name "PART NUMBER") "R0603_10K_1%_0.1W_100PPM")
        (field (name "POWER") "0.1W")
        (field (name "AUTHOR") "CERN DEM JLC")
      )
      (libsource (lib "Resistors") (part "Resistor - 1%"))
    )
    (comp (ref "R33")
      (value "220")
      (footprint "RESC1005X40N")
      (description "Resistor - 1%")
      (fields
        (field (name "PART NUMBER") "R0402_220R_1%_0.0625W_100PPM")
        (field (name "POWER") "0.0625W")
        (field (name "AUTHOR") "CERN DEM JLC")
      )
      (libsource (lib "") (part "Resistor - 1%_1"))
    )
    (comp (ref "R34")
      (value "1k")
      (footprint "RESC1005X40N")
      (description "Resistor - 1%")
      (fields
        (field (name "PART NUMBER") "R0402_1K_1%_0.0625W_100PPM")
        (field (name "POWER") "0.0625W")
        (field (name "AUTHOR") "CERN DEM JLC")
      )
      (libsource (lib "") (part "Resistor - 1%_1"))
    )
    (comp (ref "R35")
      (value "1k")
      (footprint "RESC1005X40N")
      (description "Resistor - 1%")
      (fields
        (field (name "PART NUMBER") "R0402_1K_1%_0.0625W_100PPM")
        (field (name "POWER") "0.0625W")
        (field (name "AUTHOR") "CERN DEM JLC")
      )
      (libsource (lib "") (part "Resistor - 1%_1"))
    )
    (comp (ref "R36")
      (value "1k")
      (footprint "RESC1005X40N")
      (description "Resistor - 1%")
      (fields
        (field (name "PART NUMBER") "R0402_1K_1%_0.0625W_100PPM")
        (field (name "POWER") "0.0625W")
        (field (name "AUTHOR") "CERN DEM JLC")
      )
      (libsource (lib "") (part "Resistor - 1%_1"))
    )
    (comp (ref "R37")
      (value "1k")
      (footprint "RESC1005X40N")
      (description "Resistor - 1%")
      (fields
        (field (name "PART NUMBER") "R0402_1K_1%_0.0625W_100PPM")
        (field (name "POWER") "0.0625W")
        (field (name "AUTHOR") "CERN DEM JLC")
      )
      (libsource (lib "") (part "Resistor - 1%_1"))
    )
    (comp (ref "R38")
      (value "220")
      (footprint "RESC1005X40N")
      (description "Resistor - 1%")
      (fields
        (field (name "PART NUMBER") "R0402_220R_1%_0.0625W_100PPM")
        (field (name "POWER") "0.0625W")
        (field (name "AUTHOR") "CERN DEM JLC")
      )
      (libsource (lib "") (part "Resistor - 1%_1"))
    )
    (comp (ref "R39")
      (value "10k")
      (footprint "RESC1005X40N")
      (description "Resistor - 1%")
      (fields
        (field (name "PART NUMBER") "R0402_10K_1%_0.0625W_100PPM")
        (field (name "POWER") "0.0625W")
        (field (name "AUTHOR") "CERN DEM JLC")
      )
      (libsource (lib "") (part "Resistor - 1%_1"))
    )
    (comp (ref "R40")
      (value "10k")
      (footprint "RESC1005X40N")
      (description "Resistor - 1%")
      (fields
        (field (name "PART NUMBER") "R0402_10K_1%_0.0625W_100PPM")
        (field (name "POWER") "0.0625W")
        (field (name "AUTHOR") "CERN DEM JLC")
      )
      (libsource (lib "") (part "Resistor - 1%_1"))
    )
    (comp (ref "R41")
      (value "10k")
      (footprint "RESC1005X40N")
      (description "Resistor - 1%")
      (fields
        (field (name "PART NUMBER") "R0402_10K_1%_0.0625W_100PPM")
        (field (name "POWER") "0.0625W")
        (field (name "AUTHOR") "CERN DEM JLC")
      )
      (libsource (lib "") (part "Resistor - 1%_1"))
    )
    (comp (ref "R42")
      (value "10k")
      (footprint "RESC1005X40N")
      (description "Resistor - 1%")
      (fields
        (field (name "PART NUMBER") "R0402_10K_1%_0.0625W_100PPM")
        (field (name "POWER") "0.0625W")
        (field (name "AUTHOR") "CERN DEM JLC")
      )
      (libsource (lib "") (part "Resistor - 1%_1"))
    )
    (comp (ref "R43")
      (value "3k3")
      (footprint "RESC1005X40N")
      (description "Resistor - 1%")
      (fields
        (field (name "TOLERANCE") "±1%")
        (field (name "PART NUMBER") "R0402_3K3_1%_0.0625W_100PPM")
        (field (name "POWER") "0.0625W")
        (field (name "AUTHOR") "CERN DEM JLC")
      )
      (libsource (lib "Resistors") (part "Resistor - 1%"))
    )
    (comp (ref "R44")
      (value "1k")
      (footprint "RESC1005X40N")
      (description "Resistor - 1%")
      (fields
        (field (name "TOLERANCE") "±1%")
        (field (name "PART NUMBER") "R0402_1K_1%_0.0625W_100PPM")
        (field (name "POWER") "0.0625W")
        (field (name "AUTHOR") "CERN DEM JLC")
      )
      (libsource (lib "Resistors") (part "Resistor - 1%"))
    )
    (comp (ref "R45")
      (value "1k")
      (footprint "RESC1005X40N")
      (description "Resistor - 1%")
      (fields
        (field (name "PART NUMBER") "R0402_1K_1%_0.0625W_100PPM")
        (field (name "POWER") "0.0625W")
        (field (name "AUTHOR") "CERN DEM JLC")
      )
      (libsource (lib "") (part "Resistor - 1%_1"))
    )
    (comp (ref "R46")
      (value "1k")
      (footprint "RESC1005X40N")
      (description "Resistor - 1%")
      (fields
        (field (name "PART NUMBER") "R0402_1K_1%_0.0625W_100PPM")
        (field (name "POWER") "0.0625W")
        (field (name "AUTHOR") "CERN DEM JLC")
      )
      (libsource (lib "") (part "Resistor - 1%_1"))
    )
    (comp (ref "R47")
      (value "1k")
      (footprint "RESC1005X40N")
      (description "Resistor - 1%")
      (fields
        (field (name "PART NUMBER") "R0402_1K_1%_0.0625W_100PPM")
        (field (name "POWER") "0.0625W")
        (field (name "AUTHOR") "CERN DEM JLC")
      )
      (libsource (lib "") (part "Resistor - 1%_1"))
    )
    (comp (ref "R48")
      (value "1k")
      (footprint "RESC1005X40N")
      (description "Resistor - 1%")
      (fields
        (field (name "PART NUMBER") "R0402_1K_1%_0.0625W_100PPM")
        (field (name "POWER") "0.0625W")
        (field (name "AUTHOR") "CERN DEM JLC")
      )
      (libsource (lib "") (part "Resistor - 1%_1"))
    )
    (comp (ref "R49")
      (value "10k")
      (footprint "RESC1608X55N")
      (description "Resistor - 1%")
      (fields
        (field (name "TOLERANCE") "±1%")
        (field (name "PART NUMBER") "R0603_10K_1%_0.1W_100PPM")
        (field (name "POWER") "0.1W")
        (field (name "AUTHOR") "CERN DEM JLC")
      )
      (libsource (lib "Resistors") (part "Resistor - 1%"))
    )
    (comp (ref "R50")
      (value "10k")
      (footprint "RESC1608X55N")
      (description "Resistor - 1%")
      (fields
        (field (name "TOLERANCE") "±1%")
        (field (name "PART NUMBER") "R0603_10K_1%_0.1W_100PPM")
        (field (name "POWER") "0.1W")
        (field (name "AUTHOR") "CERN DEM JLC")
      )
      (libsource (lib "Resistors") (part "Resistor - 1%"))
    )
    (comp (ref "R51")
      (value "10k")
      (footprint "RESC1608X55N")
      (description "Resistor - 1%")
      (fields
        (field (name "TOLERANCE") "±1%")
        (field (name "PART NUMBER") "R0603_10K_1%_0.1W_100PPM")
        (field (name "POWER") "0.1W")
        (field (name "AUTHOR") "CERN DEM JLC")
      )
      (libsource (lib "Resistors") (part "Resistor - 1%"))
    )
    (comp (ref "R52")
      (value "10k")
      (footprint "RESC1608X55N")
      (description "Resistor - 1%")
      (fields
        (field (name "TOLERANCE") "±1%")
        (field (name "PART NUMBER") "R0603_10K_1%_0.1W_100PPM")
        (field (name "POWER") "0.1W")
        (field (name "AUTHOR") "CERN DEM JLC")
      )
      (libsource (lib "Resistors") (part "Resistor - 1%"))
    )
    (comp (ref "R53")
      (value "1k")
      (footprint "RESC1005X40N")
      (description "Resistor - 1%")
      (fields
        (field (name "PART NUMBER") "R0402_1K_1%_0.0625W_100PPM")
        (field (name "POWER") "0.0625W")
        (field (name "AUTHOR") "CERN DEM JLC")
      )
      (libsource (lib "") (part "Resistor - 1%_1"))
    )
    (comp (ref "R54")
      (value "1k")
      (footprint "RESC1005X40N")
      (description "Resistor - 1%")
      (fields
        (field (name "PART NUMBER") "R0402_1K_1%_0.0625W_100PPM")
        (field (name "POWER") "0.0625W")
        (field (name "AUTHOR") "CERN DEM JLC")
      )
      (libsource (lib "") (part "Resistor - 1%_1"))
    )
    (comp (ref "R55")
      (value "1k")
      (footprint "RESC1005X40N")
      (description "Resistor - 1%")
      (fields
        (field (name "TOLERANCE") "±1%")
        (field (name "PART NUMBER") "R0402_1K_1%_0.0625W_100PPM")
        (field (name "POWER") "0.0625W")
        (field (name "AUTHOR") "CERN DEM JLC")
      )
      (libsource (lib "Resistors") (part "Resistor - 1%"))
    )
    (comp (ref "R56")
      (value "1k")
      (footprint "RESC1005X40N")
      (description "Resistor - 1%")
      (fields
        (field (name "PART NUMBER") "R0402_1K_1%_0.0625W_100PPM")
        (field (name "POWER") "0.0625W")
        (field (name "AUTHOR") "CERN DEM JLC")
      )
      (libsource (lib "") (part "Resistor - 1%_1"))
    )
    (comp (ref "R57")
      (value "1k")
      (footprint "RESC1005X40N")
      (description "Resistor - 1%")
      (fields
        (field (name "PART NUMBER") "R0402_1K_1%_0.0625W_100PPM")
        (field (name "POWER") "0.0625W")
        (field (name "AUTHOR") "CERN DEM JLC")
      )
      (libsource (lib "") (part "Resistor - 1%_1"))
    )
    (comp (ref "R60")
      (value "10k")
      (footprint "RESC1608X55N")
      (description "Resistor - 1%")
      (fields
        (field (name "TOLERANCE") "±1%")
        (field (name "PART NUMBER") "R0603_10K_1%_0.1W_100PPM")
        (field (name "POWER") "0.1W")
        (field (name "AUTHOR") "CERN DEM JLC")
      )
      (libsource (lib "Resistors") (part "Resistor - 1%"))
    )
    (comp (ref "R61")
      (value "510k")
      (footprint "RESC1608X55N")
      (description "Resistor - 1%")
      (fields
        (field (name "TOLERANCE") "±1%")
        (field (name "PART NUMBER") "R0603_510K_1%_0.1W_100PPM")
        (field (name "POWER") "0.1W")
        (field (name "AUTHOR") "CERN DEM JLC")
      )
      (libsource (lib "Resistors") (part "Resistor - 1%"))
    )
    (comp (ref "R62")
      (value "18k")
      (footprint "RESC1608X55N")
      (description "Resistor - 1%")
      (fields
        (field (name "TOLERANCE") "±1%")
        (field (name "PART NUMBER") "R0603_18K_1%_0.1W_100PPM")
        (field (name "POWER") "0.1W")
        (field (name "AUTHOR") "CERN DEM JLC")
      )
      (libsource (lib "Resistors") (part "Resistor - 1%"))
    )
    (comp (ref "R63")
      (value "18k")
      (footprint "RESC1608X55N")
      (description "Resistor - 1%")
      (fields
        (field (name "TOLERANCE") "±1%")
        (field (name "PART NUMBER") "R0603_18K_1%_0.1W_100PPM")
        (field (name "POWER") "0.1W")
        (field (name "AUTHOR") "CERN DEM JLC")
      )
      (libsource (lib "Resistors") (part "Resistor - 1%"))
    )
    (comp (ref "R64")
      (value "510k")
      (footprint "RESC1608X55N")
      (description "Resistor - 1%")
      (fields
        (field (name "TOLERANCE") "±1%")
        (field (name "PART NUMBER") "R0603_510K_1%_0.1W_100PPM")
        (field (name "POWER") "0.1W")
        (field (name "AUTHOR") "CERN DEM JLC")
      )
      (libsource (lib "Resistors") (part "Resistor - 1%"))
    )
    (comp (ref "R65")
      (value "18k")
      (footprint "RESC1608X55N")
      (description "Resistor - 1%")
      (fields
        (field (name "TOLERANCE") "±1%")
        (field (name "PART NUMBER") "R0603_18K_1%_0.1W_100PPM")
        (field (name "POWER") "0.1W")
        (field (name "AUTHOR") "CERN DEM JLC")
      )
      (libsource (lib "Resistors") (part "Resistor - 1%"))
    )
    (comp (ref "R66")
      (value "18k")
      (footprint "RESC1608X55N")
      (description "Resistor - 1%")
      (fields
        (field (name "TOLERANCE") "±1%")
        (field (name "PART NUMBER") "R0603_18K_1%_0.1W_100PPM")
        (field (name "POWER") "0.1W")
        (field (name "AUTHOR") "CERN DEM JLC")
      )
      (libsource (lib "Resistors") (part "Resistor - 1%"))
    )
    (comp (ref "R68")
      (value "330")
      (footprint "RESC1005X40N")
      (description "Resistor - 1%")
      (fields
        (field (name "TOLERANCE") "±1%")
        (field (name "PART NUMBER") "R0402_330R_1%_0.0625W_100PPM")
        (field (name "POWER") "0.0625W")
        (field (name "AUTHOR") "CERN DEM JLC")
      )
      (libsource (lib "Resistors") (part "Resistor - 1%"))
    )
    (comp (ref "R73")
      (value "10")
      (footprint "RESC1005X40N")
      (description "Resistor - 1%")
      (fields
        (field (name "TOLERANCE") "±1%")
        (field (name "PART NUMBER") "R0402_10R_1%_0.0625W_200PPM")
        (field (name "POWER") "0.0625W")
        (field (name "AUTHOR") "CERN DEM JLC")
      )
      (libsource (lib "Resistors") (part "Resistor - 1%"))
    )
    (comp (ref "R91")
      (value "15k")
      (footprint "RESC1608X55N")
      (description "Resistor - 1%")
      (fields
        (field (name "TOLERANCE") "±1%")
        (field (name "PART NUMBER") "R0603_15K_1%_0.1W_100PPM")
        (field (name "POWER") "0.1W")
        (field (name "AUTHOR") "CERN DEM JMW")
      )
      (libsource (lib "Resistors") (part "Resistor - 1%"))
    )
    (comp (ref "R92")
      (value "15k")
      (footprint "RESC1608X55N")
      (description "Resistor - 1%")
      (fields
        (field (name "TOLERANCE") "±1%")
        (field (name "PART NUMBER") "R0603_15K_1%_0.1W_100PPM")
        (field (name "POWER") "0.1W")
        (field (name "AUTHOR") "CERN DEM JMW")
      )
      (libsource (lib "Resistors") (part "Resistor - 1%"))
    )
    (comp (ref "R93")
      (value "15k")
      (footprint "RESC1608X55N")
      (description "Resistor - 1%")
      (fields
        (field (name "TOLERANCE") "±1%")
        (field (name "PART NUMBER") "R0603_15K_1%_0.1W_100PPM")
        (field (name "POWER") "0.1W")
        (field (name "AUTHOR") "CERN DEM JMW")
      )
      (libsource (lib "Resistors") (part "Resistor - 1%"))
    )
    (comp (ref "R101")
      (value "50k")
      (footprint "RES_SEI_HVC1206")
      (description "Resistor - 1%")
      (fields
        (field (name "TOLERANCE") "±1%")
        (field (name "PART NUMBER") "R1206_50K_1%_0.33W_100PPM_SEI_HVC")
        (field (name "POWER") "0.33W")
        (field (name "VOLTAGE") "1500V")
        (field (name "AUTHOR") "CERN DEM JLC")
      )
      (libsource (lib "Resistors") (part "Resistor - 1%"))
    )
    (comp (ref "R102")
      (value "50k")
      (footprint "RES_SEI_HVC1206")
      (description "Resistor - 1%")
      (fields
        (field (name "TOLERANCE") "±1%")
        (field (name "PART NUMBER") "R1206_50K_1%_0.33W_100PPM_SEI_HVC")
        (field (name "POWER") "0.33W")
        (field (name "VOLTAGE") "1500V")
        (field (name "AUTHOR") "CERN DEM JLC")
      )
      (libsource (lib "Resistors") (part "Resistor - 1%"))
    )
    (comp (ref "R103")
      (value "50k")
      (footprint "RES_SEI_HVC1206")
      (description "Resistor - 1%")
      (fields
        (field (name "TOLERANCE") "±1%")
        (field (name "PART NUMBER") "R1206_50K_1%_0.33W_100PPM_SEI_HVC")
        (field (name "POWER") "0.33W")
        (field (name "VOLTAGE") "1500V")
        (field (name "AUTHOR") "CERN DEM JLC")
      )
      (libsource (lib "Resistors") (part "Resistor - 1%"))
    )
    (comp (ref "R104")
      (value "50k")
      (footprint "RES_SEI_HVC1206")
      (description "Resistor - 1%")
      (fields
        (field (name "TOLERANCE") "±1%")
        (field (name "PART NUMBER") "R1206_50K_1%_0.33W_100PPM_SEI_HVC")
        (field (name "POWER") "0.33W")
        (field (name "VOLTAGE") "1500V")
        (field (name "AUTHOR") "CERN DEM JLC")
      )
      (libsource (lib "Resistors") (part "Resistor - 1%"))
    )
    (comp (ref "R107")
      (value "6k8")
      (footprint "RESC1608X55N")
      (description "Resistor - 1%")
      (fields
        (field (name "TOLERANCE") "±1%")
        (field (name "PART NUMBER") "R0603_6K8_1%_0.1W_100PPM")
        (field (name "POWER") "0.1W")
        (field (name "AUTHOR") "CERN DEM JLC")
      )
      (libsource (lib "Resistors") (part "Resistor - 1%"))
    )
    (comp (ref "R108")
      (value "6k8")
      (footprint "RESC1608X55N")
      (description "Resistor - 1%")
      (fields
        (field (name "TOLERANCE") "±1%")
        (field (name "PART NUMBER") "R0603_6K8_1%_0.1W_100PPM")
        (field (name "POWER") "0.1W")
        (field (name "AUTHOR") "CERN DEM JLC")
      )
      (libsource (lib "Resistors") (part "Resistor - 1%"))
    )
    (comp (ref "R109")
      (value "6k8")
      (footprint "RESC1608X55N")
      (description "Resistor - 1%")
      (fields
        (field (name "TOLERANCE") "±1%")
        (field (name "PART NUMBER") "R0603_6K8_1%_0.1W_100PPM")
        (field (name "POWER") "0.1W")
        (field (name "AUTHOR") "CERN DEM JLC")
      )
      (libsource (lib "Resistors") (part "Resistor - 1%"))
    )
    (comp (ref "R110")
      (value "6k8")
      (footprint "RESC1608X55N")
      (description "Resistor - 1%")
      (fields
        (field (name "TOLERANCE") "±1%")
        (field (name "PART NUMBER") "R0603_6K8_1%_0.1W_100PPM")
        (field (name "POWER") "0.1W")
        (field (name "AUTHOR") "CERN DEM JLC")
      )
      (libsource (lib "Resistors") (part "Resistor - 1%"))
    )
    (comp (ref "T1")
      (value "PBHV8560ZX")
      (footprint "SOT230P700X180-4N")
      (description "600 V, 0.5 A NPN high-voltage low VCEsat (BISS) transistor")
      (fields (field (name "MANUFACTURER") "Nexperia") (field (name "AUTHOR") "GK"))
      (libsource (lib "Tranistors_Thyristors") (part "Q_PBHV8560Z"))
    )
    (comp (ref "T2")
      (value "IXTY01N100")
      (footprint "TO228P991X238-3N-R648X546")
      (description "N-CHANNEL MOSFET WITH DIODE")
      (fields (field (name "MANUFACTURER") "IXYS") (field (name "AUTHOR") "CERN DEM JLC"))
      (libsource (lib "ICs And Semiconductors") (part "N-MOSFET-D 1G 2S 3D"))
    )
    (comp (ref "T3")
      (value "IXTY01N100")
      (footprint "TO228P991X238-3N-R648X546")
      (description "N-CHANNEL MOSFET WITH DIODE")
      (fields (field (name "MANUFACTURER") "IXYS") (field (name "AUTHOR") "CERN DEM JLC"))
      (libsource (lib "ICs And Semiconductors") (part "N-MOSFET-D 1G 2S 3D"))
    )
    (comp (ref "T4")
      (value "IXTY01N100")
      (footprint "TO228P991X238-3N-R648X546")
      (description "N-CHANNEL MOSFET WITH DIODE")
      (fields (field (name "MANUFACTURER") "IXYS") (field (name "AUTHOR") "CERN DEM JLC"))
      (libsource (lib "ICs And Semiconductors") (part "N-MOSFET-D 1G 2S 3D"))
    )
    (comp (ref "T5")
      (value "IXTY01N100")
      (footprint "TO228P991X238-3N-R648X546")
      (description "N-CHANNEL MOSFET WITH DIODE")
      (fields (field (name "MANUFACTURER") "IXYS") (field (name "AUTHOR") "CERN DEM JLC"))
      (libsource (lib "ICs And Semiconductors") (part "N-MOSFET-D 1G 2S 3D"))
    )
    (comp (ref "T6")
      (value "STN9360")
      (footprint "SOT230P700X180-4N")
      (description "PNP Transistor")
      (fields (field (name "MANUFACTURER") "STMicroelectronics") (field (name "AUTHOR") "FS"))
      (libsource (lib "templib") (part "STN9360"))
    )
    (comp (ref "T8")
      (value "BSS138LT1G")
      (footprint "SOT95P240X110-3N")
      (description "N-CHANNEL MOSFET WITH DIODE")
      (fields
        (field (name "MANUFACTURER") "ON SEMICONDUCTOR")
        (field (name "MANUFACTURER PART NUMBER") "BSS138L")
        (field (name "AUTHOR") "CERN DEM JLC")
      )
      (libsource (lib "ICs And Semiconductors") (part "N-MOSFET-D 1G 2S 3D"))
    )
    (comp (ref "T9")
      (value "BSS138LT1G")
      (footprint "SOT95P240X110-3N")
      (description "N-CHANNEL MOSFET WITH DIODE")
      (fields
        (field (name "MANUFACTURER") "ON SEMICONDUCTOR")
        (field (name "MANUFACTURER PART NUMBER") "BSS138L")
        (field (name "AUTHOR") "CERN DEM JLC")
      )
      (libsource (lib "ICs And Semiconductors") (part "N-MOSFET-D 1G 2S 3D"))
    )
    (comp (ref "T10")
      (value "BC847BS")
      (footprint "SOT65P210X110-6N")
      (description "45V 100mA Dual NPN General-Purpose Transistor")
      (fields (field (name "MANUFACTURER") "NXP SEMICONDUCTORS") (field (name "AUTHOR") "CERN DEM JMW"))
      (libsource (lib "") (part "BC847BS_1"))
    )
    (comp (ref "TP1")
      (value "~")
      (footprint "TYCO_RCT-0C")
      (description "Test Point")
      (fields
        (field (name "PART NUMBER") "TYCO_RCT-0C")
        (field (name "MANUFACTURER") "TYCO ELECTRONICS")
        (field (name "AUTHOR") "CERN DEM JLC")
      )
      (libsource (lib "Connectors") (part "Test Point"))
    )
    (comp (ref "U1")
      (value "MCP4728-E/UN")
      (footprint "MSOP-UN10_N")
      (description "12-Bit Quad Digital-to-Analog Converter with EEPROM Memory, 10-pin MSOP, Extended Temperature")
      (libsource (lib "Altium Content Vault") (part "CON-DAC-MCP4728-10"))
    )
    (comp (ref "U2")
      (value "MCP4728-E/UN")
      (footprint "MSOP-UN10_N")
      (description "12-Bit Quad Digital-to-Analog Converter with EEPROM Memory, 10-pin MSOP, Extended Temperature")
      (libsource (lib "Altium Content Vault") (part "CON-DAC-MCP4728-10"))
    )
    (comp (ref "U3")
      (value "LMV339IDR")
      (footprint "FP-D0014A-MFG")
      (description "IC QUAD LV COMPARATOR 14-SOIC")
      (libsource (lib "Altium Content Vault") (part "eccfbacc1e8e7d8f51b3e78d6364124"))
    )
  )
  (nets
    (net (code "1") (name "/CH_ID0") (class "Default")
      (node (ref "P1") (pin "26") (pinfunction "26_26") (pintype "passive"))
      (node (ref "PCBM1") (pin "10") (pinfunction "IO25_10") (pintype "bidirectional"))
    )
    (net (code "2") (name "/CH_ID1") (class "Default")
      (node (ref "P1") (pin "25") (pinfunction "25_25") (pintype "passive"))
      (node (ref "PCBM1") (pin "13") (pinfunction "IO14_13") (pintype "bidirectional"))
    )
    (net (code "3") (name "/CH_ID2") (class "Default")
      (node (ref "P1") (pin "24") (pinfunction "24_24") (pintype "passive"))
      (node (ref "PCBM1") (pin "16") (pinfunction "IO13_16") (pintype "bidirectional"))
    )
    (net (code "4") (name "/CSn") (class "Default")
      (node (ref "IC11") (pin "3") (pinfunction "~{CS}_3") (pintype "input"))
      (node (ref "PCBM1") (pin "12") (pinfunction "IO27_12") (pintype "bidirectional"))
    )
    (net (code "5") (name "/DAC_1_OUT0") (class "Default")
      (node (ref "IC8") (pin "3") (pinfunction "IN+_3") (pintype "input"))
      (node (ref "R49") (pin "1") (pinfunction "1_1") (pintype "passive"))
      (node (ref "U1") (pin "6") (pinfunction "VOUTA_6") (pintype "output"))
    )
    (net (code "6") (name "/DAC_1_OUT1") (class "Default")
      (node (ref "IC8") (pin "5") (pinfunction "IN+_5") (pintype "input"))
      (node (ref "U1") (pin "7") (pinfunction "VOUTB_7") (pintype "output"))
    )
    (net (code "7") (name "/DAC_1_OUT2") (class "Default")
      (node (ref "IC8") (pin "10") (pinfunction "IN+_10") (pintype "input"))
      (node (ref "U1") (pin "8") (pinfunction "VOUTC_8") (pintype "output"))
    )
    (net (code "8") (name "/DAC_1_OUT3") (class "Default")
      (node (ref "IC8") (pin "12") (pinfunction "IN+_12") (pintype "input"))
      (node (ref "U1") (pin "9") (pinfunction "VOUTD_9") (pintype "output"))
    )
    (net (code "9") (name "/DAC_2_OUT0") (class "Default")
      (node (ref "U2") (pin "6") (pinfunction "VOUTA_6") (pintype "output"))
      (node (ref "U3") (pin "5") (pinfunction "1IN+_5") (pintype "tri_state"))
    )
    (net (code "10") (name "/DAC_2_OUT1") (class "Default")
      (node (ref "U2") (pin "7") (pinfunction "VOUTB_7") (pintype "output"))
      (node (ref "U3") (pin "7") (pinfunction "2IN+_7") (pintype "tri_state"))
    )
    (net (code "11") (name "/DAC_2_OUT2") (class "Default")
      (node (ref "U2") (pin "8") (pinfunction "VOUTC_8") (pintype "output"))
      (node (ref "U3") (pin "11") (pinfunction "4IN+_11") (pintype "tri_state"))
    )
    (net (code "12") (name "/DAC_2_OUT3") (class "Default")
      (node (ref "U2") (pin "9") (pinfunction "VOUTD_9") (pintype "output"))
      (node (ref "U3") (pin "9") (pinfunction "3IN+_9") (pintype "tri_state"))
    )
    (net (code "13") (name "/DAC_OUT0") (class "Default")
      (node (ref "IC8") (pin "1") (pinfunction "OUT_1") (pintype "output"))
      (node (ref "R1") (pin "2") (pinfunction "2_2") (pintype "passive"))
      (node (ref "R15") (pin "2") (pinfunction "2_2") (pintype "passive"))
    )
    (net (code "14") (name "/DAC_OUT1") (class "Default")
      (node (ref "IC8") (pin "7") (pinfunction "OUT_7") (pintype "output"))
      (node (ref "R6") (pin "2") (pinfunction "2_2") (pintype "passive"))
      (node (ref "R9") (pin "2") (pinfunction "2_2") (pintype "passive"))
    )
    (net (code "15") (name "/DAC_OUT2") (class "Default")
      (node (ref "IC8") (pin "8") (pinfunction "OUT_8") (pintype "output"))
      (node (ref "R26") (pin "2") (pinfunction "2_2") (pintype "passive"))
      (node (ref "R29") (pin "2") (pinfunction "2_2") (pintype "passive"))
    )
    (net (code "16") (name "/DAC_OUT3") (class "Default")
      (node (ref "IC8") (pin "14") (pinfunction "OUT_14") (pintype "output"))
      (node (ref "R11") (pin "2") (pinfunction "2_2") (pintype "passive"))
      (node (ref "R51") (pin "2") (pinfunction "2_2") (pintype "passive"))
    )
    (net (code "17") (name "/DEBUG") (class "Default")
      (node (ref "LD3") (pin "2") (pinfunction "A_2") (pintype "passive"))
      (node (ref "PCBM1") (pin "30") (pinfunction "IO18_30") (pintype "bidirectional"))
    )
    (net (code "18") (name "/DIV_IN") (class "Default")
      (node (ref "C15") (pin "1") (pinfunction "1_1") (pintype "passive"))
      (node (ref "D11") (pin "1") (pinfunction "C_1") (pintype "passive"))
      (node (ref "D5") (pin "1") (pinfunction "C_1") (pintype "passive"))
      (node (ref "IC11") (pin "11") (pinfunction "PB0_11") (pintype "bidirectional"))
      (node (ref "P1") (pin "16") (pinfunction "16_16") (pintype "passive"))
      (node (ref "T1") (pin "1") (pinfunction "B_1") (pintype "passive"))
      (node (ref "T6") (pin "1") (pinfunction "B_1") (pintype "passive"))
    )
    (net (code "19") (name "/DIV_OUT") (class "Default")
      (node (ref "C15") (pin "2") (pinfunction "2_2") (pintype "passive"))
      (node (ref "IC4") (pin "6") (pinfunction "6_6") (pintype "passive"))
      (node (ref "P1") (pin "19") (pinfunction "19_19") (pintype "passive"))
      (node (ref "R3") (pin "2") (pinfunction "2_2") (pintype "passive"))
    )
    (net (code "20") (name "/ESP_EN") (class "Default")
      (node (ref "C24") (pin "2") (pinfunction "2_2") (pintype "passive"))
      (node (ref "PCBM1") (pin "3") (pinfunction "EN_3") (pintype "input"))
      (node (ref "R4") (pin "2") (pinfunction "2_2") (pintype "passive"))
      (node (ref "T10") (pin "6") (pinfunction "C_6") (pintype "passive"))
    )
    (net (code "21") (name "/GEM_O0") (class "Default")
      (node (ref "P1") (pin "1") (pinfunction "1_1") (pintype "passive"))
      (node (ref "R101") (pin "2") (pinfunction "2_2") (pintype "passive"))
    )
    (net (code "22") (name "/GEM_O1") (class "Default")
      (node (ref "P1") (pin "3") (pinfunction "3_3") (pintype "passive"))
      (node (ref "R102") (pin "2") (pinfunction "2_2") (pintype "passive"))
    )
    (net (code "23") (name "/GEM_O2") (class "Default")
      (node (ref "P1") (pin "2") (pinfunction "2_2") (pintype "passive"))
      (node (ref "R103") (pin "2") (pinfunction "2_2") (pintype "passive"))
    )
    (net (code "24") (name "/GEM_O3") (class "Default")
      (node (ref "P1") (pin "4") (pinfunction "4_4") (pintype "passive"))
      (node (ref "R104") (pin "2") (pinfunction "2_2") (pintype "passive"))
    )
    (net (code "25") (name "/GPIO0{slash}EMAC_CLKIN") (class "Default")
      (node (ref "D16") (pin "2") (pinfunction "A_2") (pintype "passive"))
      (node (ref "PCBM1") (pin "25") (pinfunction "IO0_25") (pintype "bidirectional"))
      (node (ref "R30") (pin "1") (pinfunction "1_1") (pintype "passive"))
    )
    (net (code "26") (name "/GPIO2{slash}HS2_DATA0") (class "Default")
      (node (ref "D16") (pin "1") (pinfunction "A_1") (pintype "passive"))
      (node (ref "PCBM1") (pin "24") (pinfunction "IO2_24") (pintype "bidirectional"))
    )
    (net (code "27") (name "/HVQN_C") (class "Default")
      (node (ref "P1") (pin "15") (pinfunction "15_15") (pintype "passive"))
      (node (ref "R21") (pin "1") (pinfunction "1_1") (pintype "passive"))
      (node (ref "T1") (pin "2") (pinfunction "C_2") (pintype "passive"))
      (node (ref "T1") (pin "4") (pinfunction "C_4") (pintype "passive"))
    )
    (net (code "28") (name "/HVQP_C") (class "Default")
      (node (ref "P1") (pin "12") (pinfunction "12_12") (pintype "passive"))
      (node (ref "T6") (pin "2") (pinfunction "C_2") (pintype "passive"))
      (node (ref "T6") (pin "4") (pinfunction "C_4") (pintype "passive"))
    )
    (net (code "29") (name "/HVQP_E") (class "Default")
      (node (ref "D10") (pin "1") (pinfunction "C_1") (pintype "passive"))
      (node (ref "P1") (pin "8") (pinfunction "8_8") (pintype "passive"))
      (node (ref "T6") (pin "3") (pinfunction "E_3") (pintype "passive"))
    )
    (net (code "30") (name "/HVSET0") (class "Default")
      (node (ref "PCBM1") (pin "11") (pinfunction "IO26_11") (pintype "bidirectional"))
      (node (ref "R27") (pin "2") (pinfunction "2_2") (pintype "passive"))
      (node (ref "R68") (pin "1") (pinfunction "1_1") (pintype "passive"))
    )
    (net (code "31") (name "/HV_LIM") (class "Default")
      (node (ref "D20") (pin "1") (pinfunction "C_1") (pintype "passive"))
      (node (ref "D21") (pin "1") (pinfunction "C_1") (pintype "passive"))
      (node (ref "D22") (pin "1") (pinfunction "C_1") (pintype "passive"))
      (node (ref "D23") (pin "1") (pinfunction "C_1") (pintype "passive"))
      (node (ref "D24") (pin "1") (pinfunction "C_1") (pintype "passive"))
    )
    (net (code "32") (name "/HV_Meas") (class "Default")
      (node (ref "C18") (pin "2") (pinfunction "2_2") (pintype "passive"))
      (node (ref "IC2") (pin "4") (pinfunction "AIN0_4") (pintype "input"))
      (node (ref "R22") (pin "2") (pinfunction "2_2") (pintype "passive"))
      (node (ref "R23") (pin "2") (pinfunction "2_2") (pintype "passive"))
    )
    (net (code "33") (name "/I2C1_SCL") (class "Default")
      (node (ref "IC2") (pin "10") (pinfunction "SCL_10") (pintype "input"))
      (node (ref "IC7") (pin "10") (pinfunction "SCL_10") (pintype "input"))
      (node (ref "PCBM1") (pin "36") (pinfunction "IO22_36") (pintype "bidirectional"))
      (node (ref "R12") (pin "1") (pinfunction "1_1") (pintype "passive"))
      (node (ref "T8") (pin "2") (pinfunction "S_2") (pintype "passive"))
    )
    (net (code "34") (name "/I2C1_SDA") (class "Default")
      (node (ref "D6") (pin "2") (pinfunction "A_2") (pintype "passive"))
      (node (ref "IC2") (pin "9") (pinfunction "SDA_9") (pintype "bidirectional"))
      (node (ref "IC7") (pin "9") (pinfunction "SDA_9") (pintype "bidirectional"))
      (node (ref "PCBM1") (pin "33") (pinfunction "IO21_33") (pintype "bidirectional"))
      (node (ref "R13") (pin "1") (pinfunction "1_1") (pintype "passive"))
      (node (ref "T9") (pin "2") (pinfunction "S_2") (pintype "passive"))
    )
    (net (code "35") (name "/I2C2_SCL") (class "Default")
      (node (ref "PCBM1") (pin "37") (pinfunction "IO23_37") (pintype "bidirectional"))
      (node (ref "R53") (pin "1") (pinfunction "1_1") (pintype "passive"))
      (node (ref "U2") (pin "2") (pinfunction "SCL_2") (pintype "input"))
    )
    (net (code "36") (name "/I2C2_SDA") (class "Default")
      (node (ref "PCBM1") (pin "31") (pinfunction "IO19_31") (pintype "bidirectional"))
      (node (ref "R54") (pin "1") (pinfunction "1_1") (pintype "passive"))
      (node (ref "U2") (pin "3") (pinfunction "SDA_3") (pintype "bidirectional"))
    )
    (net (code "37") (name "/I_Meas0") (class "Default")
      (node (ref "IC1") (pin "8") (pinfunction "OUT_8") (pintype "output"))
      (node (ref "R47") (pin "1") (pinfunction "1_1") (pintype "passive"))
      (node (ref "R92") (pin "2") (pinfunction "2_2") (pintype "passive"))
    )
    (net (code "38") (name "/I_Meas1") (class "Default")
      (node (ref "IC1") (pin "1") (pinfunction "OUT_1") (pintype "output"))
      (node (ref "R16") (pin "2") (pinfunction "2_2") (pintype "passive"))
      (node (ref "R45") (pin "1") (pinfunction "1_1") (pintype "passive"))
    )
    (net (code "39") (name "/I_Meas2") (class "Default")
      (node (ref "IC1") (pin "14") (pinfunction "OUT_14") (pintype "output"))
      (node (ref "R48") (pin "1") (pinfunction "1_1") (pintype "passive"))
      (node (ref "R93") (pin "2") (pinfunction "2_2") (pintype "passive"))
    )
    (net (code "40") (name "/I_Meas3") (class "Default")
      (node (ref "IC1") (pin "7") (pinfunction "OUT_7") (pintype "output"))
      (node (ref "R46") (pin "1") (pinfunction "1_1") (pintype "passive"))
      (node (ref "R91") (pin "2") (pinfunction "2_2") (pintype "passive"))
    )
    (net (code "41") (name "/I_Meas_sens0") (class "Default")
      (node (ref "D2") (pin "3") (pinfunction "COMAC_3") (pintype "passive"))
      (node (ref "R109") (pin "1") (pinfunction "1_1") (pintype "passive"))
      (node (ref "R7") (pin "2") (pinfunction "2_2") (pintype "passive"))
      (node (ref "T2") (pin "2") (pinfunction "S_2") (pintype "passive"))
      (node (ref "U3") (pin "4") (pinfunction "1IN-_4") (pintype "tri_state"))
    )
    (net (code "42") (name "/I_Meas_sens1") (class "Default")
      (node (ref "D1") (pin "3") (pinfunction "COMAC_3") (pintype "passive"))
      (node (ref "R107") (pin "1") (pinfunction "1_1") (pintype "passive"))
      (node (ref "R8") (pin "2") (pinfunction "2_2") (pintype "passive"))
      (node (ref "T3") (pin "2") (pinfunction "S_2") (pintype "passive"))
      (node (ref "U3") (pin "6") (pinfunction "2IN-_6") (pintype "tri_state"))
    )
    (net (code "43") (name "/I_Meas_sens2") (class "Default")
      (node (ref "D3") (pin "3") (pinfunction "COMAC_3") (pintype "passive"))
      (node (ref "R110") (pin "1") (pinfunction "1_1") (pintype "passive"))
      (node (ref "R28") (pin "2") (pinfunction "2_2") (pintype "passive"))
      (node (ref "T4") (pin "2") (pinfunction "S_2") (pintype "passive"))
      (node (ref "U3") (pin "10") (pinfunction "4IN-_10") (pintype "tri_state"))
    )
    (net (code "44") (name "/I_Meas_sens3") (class "Default")
      (node (ref "D4") (pin "3") (pinfunction "COMAC_3") (pintype "passive"))
      (node (ref "R10") (pin "2") (pinfunction "2_2") (pintype "passive"))
      (node (ref "R108") (pin "1") (pinfunction "1_1") (pintype "passive"))
      (node (ref "T5") (pin "2") (pinfunction "S_2") (pintype "passive"))
      (node (ref "U3") (pin "8") (pinfunction "3IN-_8") (pintype "tri_state"))
    )
    (net (code "45") (name "/OC_0") (class "Default")
      (node (ref "PCBM1") (pin "7") (pinfunction "IO35_7") (pintype "bidirectional"))
      (node (ref "R36") (pin "1") (pinfunction "1_1") (pintype "passive"))
      (node (ref "U3") (pin "2") (pinfunction "1OUT_2") (pintype "open_collector"))
    )
    (net (code "46") (name "/OC_1") (class "Default")
      (node (ref "PCBM1") (pin "6") (pinfunction "IO34_6") (pintype "bidirectional"))
      (node (ref "R37") (pin "1") (pinfunction "1_1") (pintype "passive"))
      (node (ref "U3") (pin "1") (pinfunction "2OUT_1") (pintype "open_collector"))
    )
    (net (code "47") (name "/OC_2") (class "Default")
      (node (ref "PCBM1") (pin "9") (pinfunction "IO33_9") (pintype "bidirectional"))
      (node (ref "R56") (pin "1") (pinfunction "1_1") (pintype "passive"))
      (node (ref "U3") (pin "13") (pinfunction "4OUT_13") (pintype "open_collector"))
    )
    (net (code "48") (name "/OC_3") (class "Default")
      (node (ref "PCBM1") (pin "8") (pinfunction "IO32_8") (pintype "bidirectional"))
      (node (ref "R57") (pin "1") (pinfunction "1_1") (pintype "passive"))
      (node (ref "U3") (pin "14") (pinfunction "3OUT_14") (pintype "open_collector"))
    )
    (net (code "49") (name "/P3V3_HV") (class "Default")
      (node (ref "C16") (pin "2") (pinfunction "2_2") (pintype "passive"))
      (node (ref "C21") (pin "2") (pinfunction "2_2") (pintype "passive"))
      (node (ref "C22") (pin "2") (pinfunction "2_2") (pintype "passive"))
      (node (ref "C23") (pin "2") (pinfunction "2_2") (pintype "passive"))
      (node (ref "C26") (pin "2") (pinfunction "2_2") (pintype "passive"))
      (node (ref "C39") (pin "2") (pinfunction "2_2") (pintype "passive"))
      (node (ref "C42") (pin "2") (pinfunction "2_2") (pintype "passive"))
      (node (ref "C48") (pin "2") (pinfunction "2_2") (pintype "passive"))
      (node (ref "C8") (pin "1") (pinfunction "1_1") (pintype "passive"))
      (node (ref "C9") (pin "2") (pinfunction "2_2") (pintype "passive"))
      (node (ref "IC1") (pin "4") (pinfunction "V+_4") (pintype "power_in"))
      (node (ref "IC11") (pin "1") (pinfunction "VL_1") (pintype "power_in"))
      (node (ref "IC11") (pin "7") (pinfunction "~{SHDN}_7") (pintype "input"))
      (node (ref "IC2") (pin "8") (pinfunction "VDD_8") (pintype "power_in"))
      (node (ref "IC6") (pin "2") (pinfunction "OUT_2") (pintype "power_in"))
      (node (ref "IC6") (pin "4") (pinfunction "OUT_4") (pintype "power_in"))
      (node (ref "IC7") (pin "1") (pinfunction "ADDR_1") (pintype "input"))
      (node (ref "IC7") (pin "8") (pinfunction "VDD_8") (pintype "power_in"))
      (node (ref "LD2") (pin "2") (pinfunction "A_2") (pintype "passive"))
      (node (ref "PCBM1") (pin "2") (pinfunction "VDD33_2") (pintype "power_in"))
      (node (ref "R12") (pin "2") (pinfunction "2_2") (pintype "passive"))
      (node (ref "R13") (pin "2") (pinfunction "2_2") (pintype "passive"))
      (node (ref "R25") (pin "2") (pinfunction "2_2") (pintype "passive"))
      (node (ref "R27") (pin "1") (pinfunction "1_1") (pintype "passive"))
      (node (ref "R30") (pin "2") (pinfunction "2_2") (pintype "passive"))
      (node (ref "R36") (pin "2") (pinfunction "2_2") (pintype "passive"))
      (node (ref "R37") (pin "2") (pinfunction "2_2") (pintype "passive"))
      (node (ref "R4") (pin "1") (pinfunction "1_1") (pintype "passive"))
      (node (ref "R40") (pin "2") (pinfunction "2_2") (pintype "passive"))
      (node (ref "R42") (pin "2") (pinfunction "2_2") (pintype "passive"))
      (node (ref "R53") (pin "2") (pinfunction "2_2") (pintype "passive"))
      (node (ref "R54") (pin "2") (pinfunction "2_2") (pintype "passive"))
      (node (ref "R56") (pin "2") (pinfunction "2_2") (pintype "passive"))
      (node (ref "R57") (pin "2") (pinfunction "2_2") (pintype "passive"))
      (node (ref "U2") (pin "1") (pinfunction "VDD_1") (pintype "power_in"))
      (node (ref "U3") (pin "3") (pinfunction "VCC+_3") (pintype "power_in"))
    )
    (net (code "50") (name "/P5V0_HV") (class "Default")
      (node (ref "C27") (pin "2") (pinfunction "2_2") (pintype "passive"))
      (node (ref "C30") (pin "2") (pinfunction "2_2") (pintype "passive"))
      (node (ref "D17") (pin "1") (pinfunction "C_1") (pintype "passive"))
      (node (ref "IC12") (pin "5") (pinfunction "VIN_5") (pintype "input"))
      (node (ref "IC6") (pin "3") (pinfunction "IN_3") (pintype "input"))
      (node (ref "J1") (pin "4") (pinfunction "4_4") (pintype "bidirectional"))
      (node (ref "L1") (pin "1") (pinfunction "1_1") (pintype "passive"))
      (node (ref "LD1") (pin "2") (pinfunction "A_2") (pintype "passive"))
      (node (ref "R32") (pin "1") (pinfunction "1_1") (pintype "passive"))
      (node (ref "R39") (pin "2") (pinfunction "2_2") (pintype "passive"))
      (node (ref "R41") (pin "2") (pinfunction "2_2") (pintype "passive"))
      (node (ref "R65") (pin "2") (pinfunction "2_2") (pintype "passive"))
      (node (ref "R73") (pin "1") (pinfunction "1_1") (pintype "passive"))
    )
    (net (code "51") (name "/P5V0_IN") (class "Default")
      (node (ref "C6") (pin "2") (pinfunction "2_2") (pintype "passive"))
      (node (ref "IC5") (pin "1") (pinfunction "+Vin_1") (pintype "power_in"))
      (node (ref "P1") (pin "31") (pinfunction "31_31") (pintype "passive"))
    )
    (net (code "52") (name "/SCK") (class "Default")
      (node (ref "IC11") (pin "2") (pinfunction "SCK_2") (pintype "input"))
      (node (ref "PCBM1") (pin "29") (pinfunction "IO5_29") (pintype "bidirectional"))
    )
    (net (code "53") (name "/SCL1") (class "Default")
      (node (ref "R39") (pin "1") (pinfunction "1_1") (pintype "passive"))
      (node (ref "T8") (pin "3") (pinfunction "D_3") (pintype "passive"))
      (node (ref "U1") (pin "2") (pinfunction "SCL_2") (pintype "input"))
    )
    (net (code "54") (name "/SDA1") (class "Default")
      (node (ref "D6") (pin "3") (pinfunction "COMC_3") (pintype "passive"))
      (node (ref "R41") (pin "1") (pinfunction "1_1") (pintype "passive"))
      (node (ref "T9") (pin "3") (pinfunction "D_3") (pintype "passive"))
      (node (ref "U1") (pin "3") (pinfunction "SDA_3") (pintype "bidirectional"))
    )
    (net (code "55") (name "/SDI") (class "Default")
      (node (ref "IC11") (pin "4") (pinfunction "SDI_4") (pintype "input"))
      (node (ref "PCBM1") (pin "23") (pinfunction "IO15_23") (pintype "bidirectional"))
    )
    (net (code "56") (name "/SDO") (class "Default")
      (node (ref "IC11") (pin "5") (pinfunction "SDO_5") (pintype "output"))
      (node (ref "PCBM1") (pin "26") (pinfunction "IO4_26") (pintype "bidirectional"))
    )
    (net (code "57") (name "/U0RXD") (class "Default")
      (node (ref "PCBM1") (pin "34") (pinfunction "RXD0_34") (pintype "bidirectional"))
      (node (ref "R5") (pin "2") (pinfunction "2_2") (pintype "passive"))
    )
    (net (code "58") (name "/U0TXD") (class "Default")
      (node (ref "PCBM1") (pin "35") (pinfunction "TXD0_35") (pintype "bidirectional"))
      (node (ref "R33") (pin "2") (pinfunction "2_2") (pintype "passive"))
    )
    (net (code "59") (name "/VUART_CTS") (class "Default")
      (node (ref "J1") (pin "5") (pinfunction "5_5") (pintype "bidirectional+no_connect"))
    )
    (net (code "60") (name "/VUART_DTR") (class "Default")
      (node (ref "J1") (pin "1") (pinfunction "1_1") (pintype "bidirectional"))
      (node (ref "R34") (pin "1") (pinfunction "1_1") (pintype "passive"))
      (node (ref "T10") (pin "4") (pinfunction "E_4") (pintype "passive"))
    )
    (net (code "61") (name "/VUART_RTS") (class "Default")
      (node (ref "J1") (pin "7") (pinfunction "7_7") (pintype "bidirectional"))
      (node (ref "R35") (pin "1") (pinfunction "1_1") (pintype "passive"))
      (node (ref "T10") (pin "1") (pinfunction "E_1") (pintype "passive"))
    )
    (net (code "62") (name "/VUART_Rx") (class "Default")
      (node (ref "J1") (pin "2") (pinfunction "2_2") (pintype "bidirectional"))
      (node (ref "R33") (pin "1") (pinfunction "1_1") (pintype "passive"))
    )
    (net (code "63") (name "/VUART_Tx") (class "Default")
      (node (ref "J1") (pin "3") (pinfunction "3_3") (pintype "bidirectional"))
      (node (ref "R5") (pin "1") (pinfunction "1_1") (pintype "passive"))
    )
    (net (code "64") (name "/wiper") (class "Default")
      (node (ref "D7") (pin "2") (pinfunction "A_2") (pintype "passive"))
      (node (ref "IC11") (pin "12") (pinfunction "PW0_12") (pintype "bidirectional"))
      (node (ref "IC4") (pin "4") (pinfunction "4_4") (pintype "passive"))
      (node (ref "R3") (pin "1") (pinfunction "1_1") (pintype "passive"))
    )
    (net (code "65") (name "GND") (class "Default")
      (node (ref "C6") (pin "1") (pinfunction "1_1") (pintype "passive"))
      (node (ref "IC5") (pin "2") (pinfunction "-Vin_2") (pintype "power_in"))
      (node (ref "P1") (pin "32") (pinfunction "32_32") (pintype "passive"))
    )
    (net (code "66") (name "GND_HV") (class "Default")
      (node (ref "B3") (pin "1") (pinfunction "1_1") (pintype "bidirectional"))
      (node (ref "C1") (pin "1") (pinfunction "1_1") (pintype "passive"))
      (node (ref "C10") (pin "1") (pinfunction "1_1") (pintype "passive"))
      (node (ref "C11") (pin "1") (pinfunction "1_1") (pintype "passive"))
      (node (ref "C12") (pin "1") (pinfunction "1_1") (pintype "passive"))
      (node (ref "C13") (pin "1") (pinfunction "1_1") (pintype "passive"))
      (node (ref "C14") (pin "1") (pinfunction "1_1") (pintype "passive"))
      (node (ref "C16") (pin "1") (pinfunction "1_1") (pintype "passive"))
      (node (ref "C17") (pin "1") (pinfunction "1_1") (pintype "passive"))
      (node (ref "C18") (pin "1") (pinfunction "1_1") (pintype "passive"))
      (node (ref "C19") (pin "1") (pinfunction "1_1") (pintype "passive"))
      (node (ref "C2") (pin "1") (pinfunction "1_1") (pintype "passive"))
      (node (ref "C20") (pin "1") (pinfunction "1_1") (pintype "passive"))
      (node (ref "C21") (pin "1") (pinfunction "1_1") (pintype "passive"))
      (node (ref "C22") (pin "1") (pinfunction "1_1") (pintype "passive"))
      (node (ref "C23") (pin "1") (pinfunction "1_1") (pintype "passive"))
      (node (ref "C24") (pin "1") (pinfunction "1_1") (pintype "passive"))
      (node (ref "C26") (pin "1") (pinfunction "1_1") (pintype "passive"))
      (node (ref "C27") (pin "1") (pinfunction "1_1") (pintype "passive"))
      (node (ref "C28") (pin "1") (pinfunction "1_1") (pintype "passive"))
      (node (ref "C29") (pin "1") (pinfunction "1_1") (pintype "passive"))
      (node (ref "C3") (pin "1") (pinfunction "1_1") (pintype "passive"))
      (node (ref "C30") (pin "1") (pinfunction "1_1") (pintype "passive"))
      (node (ref "C39") (pin "1") (pinfunction "1_1") (pintype "passive"))
      (node (ref "C4") (pin "1") (pinfunction "1_1") (pintype "passive"))
      (node (ref "C42") (pin "1") (pinfunction "1_1") (pintype "passive"))
      (node (ref "C48") (pin "1") (pinfunction "1_1") (pintype "passive"))
      (node (ref "C49") (pin "1") (pinfunction "1_1") (pintype "passive"))
      (node (ref "C5") (pin "1") (pinfunction "1_1") (pintype "passive"))
      (node (ref "C7") (pin "1") (pinfunction "1_1") (pintype "passive"))
      (node (ref "C8") (pin "2") (pinfunction "2_2") (pintype "passive"))
      (node (ref "C9") (pin "1") (pinfunction "1_1") (pintype "passive"))
      (node (ref "D1") (pin "1") (pinfunction "A_1") (pintype "passive"))
      (node (ref "D10") (pin "2") (pinfunction "A_2") (pintype "passive"))
      (node (ref "D11") (pin "2") (pinfunction "A_2") (pintype "passive"))
      (node (ref "D12") (pin "2") (pinfunction "A_2") (pintype "passive"))
      (node (ref "D13") (pin "2") (pinfunction "A_2") (pintype "passive"))
      (node (ref "D14") (pin "2") (pinfunction "A_2") (pintype "passive"))
      (node (ref "D15") (pin "2") (pinfunction "A_2") (pintype "passive"))
      (node (ref "D2") (pin "1") (pinfunction "A_1") (pintype "passive"))
      (node (ref "D26") (pin "2") (pinfunction "A_2") (pintype "passive"))
      (node (ref "D3") (pin "1") (pinfunction "A_1") (pintype "passive"))
      (node (ref "D4") (pin "1") (pinfunction "A_1") (pintype "passive"))
      (node (ref "D5") (pin "2") (pinfunction "A_2") (pintype "passive"))
      (node (ref "D9") (pin "2") (pinfunction "A_2") (pintype "passive"))
      (node (ref "IC1") (pin "11") (pinfunction "GND_11") (pintype "power_in"))
      (node (ref "IC10") (pin "2") (pinfunction "GND_2") (pintype "passive"))
      (node (ref "IC11") (pin "10") (pinfunction "V-_10") (pintype "power_in"))
      (node (ref "IC11") (pin "6") (pinfunction "~{WLAT}_6") (pintype "input"))
      (node (ref "IC11") (pin "9") (pinfunction "DGND_9") (pintype "power_in"))
      (node (ref "IC12") (pin "2") (pinfunction "GND_2") (pintype "power_in"))
      (node (ref "IC2") (pin "1") (pinfunction "ADDR_1") (pintype "input"))
      (node (ref "IC2") (pin "3") (pinfunction "GND_3") (pintype "power_in"))
      (node (ref "IC4") (pin "2") (pinfunction "K_2") (pintype "input"))
      (node (ref "IC5") (pin "14") (pinfunction "-Vout_14") (pintype "power_in"))
      (node (ref "IC7") (pin "3") (pinfunction "GND_3") (pintype "power_in"))
      (node (ref "IC8") (pin "11") (pinfunction "V-_11") (pintype "power_in"))
      (node (ref "J1") (pin "6") (pinfunction "6_6") (pintype "bidirectional"))
      (node (ref "P1") (pin "22") (pinfunction "22_22") (pintype "passive"))
      (node (ref "P1") (pin "23") (pinfunction "23_23") (pintype "passive"))
      (node (ref "PCBM1") (pin "1") (pinfunction "GND_1") (pintype "power_in"))
      (node (ref "PCBM1") (pin "15") (pinfunction "GND_15") (pintype "power_in"))
      (node (ref "PCBM1") (pin "38") (pinfunction "GND_38") (pintype "power_in"))
      (node (ref "PCBM1") (pin "39") (pinfunction "GND_39") (pintype "power_in"))
      (node (ref "R10") (pin "1") (pinfunction "1_1") (pintype "passive"))
      (node (ref "R14") (pin "1") (pinfunction "1_1") (pintype "passive"))
      (node (ref "R17") (pin "1") (pinfunction "1_1") (pintype "passive"))
      (node (ref "R18") (pin "1") (pinfunction "1_1") (pintype "passive"))
      (node (ref "R19") (pin "1") (pinfunction "1_1") (pintype "passive"))
      (node (ref "R2") (pin "1") (pinfunction "1_1") (pintype "passive"))
      (node (ref "R20") (pin "1") (pinfunction "1_1") (pintype "passive"))
      (node (ref "R23") (pin "1") (pinfunction "1_1") (pintype "passive"))
      (node (ref "R24") (pin "1") (pinfunction "1_1") (pintype "passive"))
      (node (ref "R28") (pin "1") (pinfunction "1_1") (pintype "passive"))
      (node (ref "R31") (pin "1") (pinfunction "1_1") (pintype "passive"))
      (node (ref "R43") (pin "1") (pinfunction "1_1") (pintype "passive"))
      (node (ref "R44") (pin "1") (pinfunction "1_1") (pintype "passive"))
      (node (ref "R50") (pin "1") (pinfunction "1_1") (pintype "passive"))
      (node (ref "R52") (pin "1") (pinfunction "1_1") (pintype "passive"))
      (node (ref "R55") (pin "2") (pinfunction "2_2") (pintype "passive"))
      (node (ref "R60") (pin "1") (pinfunction "1_1") (pintype "passive"))
      (node (ref "R62") (pin "1") (pinfunction "1_1") (pintype "passive"))
      (node (ref "R66") (pin "1") (pinfunction "1_1") (pintype "passive"))
      (node (ref "R7") (pin "1") (pinfunction "1_1") (pintype "passive"))
      (node (ref "R8") (pin "1") (pinfunction "1_1") (pintype "passive"))
      (node (ref "T1") (pin "3") (pinfunction "E_3") (pintype "passive"))
      (node (ref "TP1") (pin "1") (pinfunction "1_1") (pintype "bidirectional"))
      (node (ref "U1") (pin "10") (pinfunction "VSS_10") (pintype "power_in"))
      (node (ref "U1") (pin "4") (pinfunction "~{LDAC}_4") (pintype "input"))
      (node (ref "U2") (pin "10") (pinfunction "VSS_10") (pintype "power_in"))
      (node (ref "U2") (pin "4") (pinfunction "~{LDAC}_4") (pintype "input"))
      (node (ref "U3") (pin "12") (pinfunction "GND_12") (pintype "power_in"))
    )
    (net (code "67") (name "Net-(D8-A)") (class "Default")
      (node (ref "D8") (pin "2") (pinfunction "A_2") (pintype "passive"))
      (node (ref "IC12") (pin "1") (pinfunction "SW_1") (pintype "output"))
      (node (ref "L1") (pin "2") (pinfunction "2_2") (pintype "passive"))
    )
    (net (code "68") (name "Net-(D12-C)") (class "Default")
      (node (ref "C1") (pin "2") (pinfunction "2_2") (pintype "passive"))
      (node (ref "D12") (pin "1") (pinfunction "C_1") (pintype "passive"))
      (node (ref "D2") (pin "2") (pinfunction "C_2") (pintype "passive"))
      (node (ref "R15") (pin "1") (pinfunction "1_1") (pintype "passive"))
      (node (ref "T2") (pin "1") (pinfunction "G_1") (pintype "passive"))
    )
    (net (code "69") (name "Net-(D13-C)") (class "Default")
      (node (ref "C2") (pin "2") (pinfunction "2_2") (pintype "passive"))
      (node (ref "D1") (pin "2") (pinfunction "C_2") (pintype "passive"))
      (node (ref "D13") (pin "1") (pinfunction "C_1") (pintype "passive"))
      (node (ref "R9") (pin "1") (pinfunction "1_1") (pintype "passive"))
      (node (ref "T3") (pin "1") (pinfunction "G_1") (pintype "passive"))
    )
    (net (code "70") (name "Net-(D14-C)") (class "Default")
      (node (ref "C5") (pin "2") (pinfunction "2_2") (pintype "passive"))
      (node (ref "D14") (pin "1") (pinfunction "C_1") (pintype "passive"))
      (node (ref "D3") (pin "2") (pinfunction "C_2") (pintype "passive"))
      (node (ref "R29") (pin "1") (pinfunction "1_1") (pintype "passive"))
      (node (ref "T4") (pin "1") (pinfunction "G_1") (pintype "passive"))
    )
    (net (code "71") (name "Net-(D15-C)") (class "Default")
      (node (ref "C4") (pin "2") (pinfunction "2_2") (pintype "passive"))
      (node (ref "D15") (pin "1") (pinfunction "C_1") (pintype "passive"))
      (node (ref "D4") (pin "2") (pinfunction "C_2") (pintype "passive"))
      (node (ref "R11") (pin "1") (pinfunction "1_1") (pintype "passive"))
      (node (ref "T5") (pin "1") (pinfunction "G_1") (pintype "passive"))
    )
    (net (code "72") (name "Net-(D16A-COMC)") (class "Default")
      (node (ref "D16") (pin "3") (pinfunction "COMC_3") (pintype "passive"))
      (node (ref "R38") (pin "2") (pinfunction "2_2") (pintype "passive"))
    )
    (net (code "73") (name "Net-(D17-A)") (class "Default")
      (node (ref "B2") (pin "1") (pinfunction "1_1") (pintype "bidirectional"))
      (node (ref "C49") (pin "2") (pinfunction "2_2") (pintype "passive"))
      (node (ref "D17") (pin "2") (pinfunction "A_2") (pintype "passive"))
      (node (ref "IC5") (pin "16") (pinfunction "+Vout_16") (pintype "power_in"))
    )
    (net (code "74") (name "Net-(D20-A)") (class "Default")
      (node (ref "D20") (pin "2") (pinfunction "A_2") (pintype "passive"))
      (node (ref "R101") (pin "1") (pinfunction "1_1") (pintype "passive"))
      (node (ref "T2") (pin "3") (pinfunction "D_3") (pintype "passive"))
    )
    (net (code "75") (name "Net-(D21-A)") (class "Default")
      (node (ref "D21") (pin "2") (pinfunction "A_2") (pintype "passive"))
      (node (ref "R102") (pin "1") (pinfunction "1_1") (pintype "passive"))
      (node (ref "T3") (pin "3") (pinfunction "D_3") (pintype "passive"))
    )
    (net (code "76") (name "Net-(D22-A)") (class "Default")
      (node (ref "D22") (pin "2") (pinfunction "A_2") (pintype "passive"))
      (node (ref "R103") (pin "1") (pinfunction "1_1") (pintype "passive"))
      (node (ref "T4") (pin "3") (pinfunction "D_3") (pintype "passive"))
    )
    (net (code "77") (name "Net-(D23-A)") (class "Default")
      (node (ref "D23") (pin "2") (pinfunction "A_2") (pintype "passive"))
      (node (ref "R104") (pin "1") (pinfunction "1_1") (pintype "passive"))
      (node (ref "T5") (pin "3") (pinfunction "D_3") (pintype "passive"))
    )
    (net (code "78") (name "Net-(D24-A)") (class "Default")
      (node (ref "D24") (pin "2") (pinfunction "A_2") (pintype "passive"))
      (node (ref "D26") (pin "1") (pinfunction "C_1") (pintype "passive"))
    )
    (net (code "79") (name "Net-(IC1A-IN+)") (class "Default")
      (node (ref "IC1") (pin "3") (pinfunction "IN+_3") (pintype "input"))
      (node (ref "R107") (pin "2") (pinfunction "2_2") (pintype "passive"))
    )
    (net (code "80") (name "Net-(IC1A-IN-)") (class "Default")
      (node (ref "IC1") (pin "2") (pinfunction "IN-_2") (pintype "input"))
      (node (ref "R16") (pin "1") (pinfunction "1_1") (pintype "passive"))
      (node (ref "R17") (pin "2") (pinfunction "2_2") (pintype "passive"))
    )
    (net (code "81") (name "Net-(IC1B-IN+)") (class "Default")
      (node (ref "IC1") (pin "5") (pinfunction "IN+_5") (pintype "input"))
      (node (ref "R108") (pin "2") (pinfunction "2_2") (pintype "passive"))
    )
    (net (code "82") (name "Net-(IC1B-IN-)") (class "Default")
      (node (ref "IC1") (pin "6") (pinfunction "IN-_6") (pintype "input"))
      (node (ref "R18") (pin "2") (pinfunction "2_2") (pintype "passive"))
      (node (ref "R91") (pin "1") (pinfunction "1_1") (pintype "passive"))
    )
    (net (code "83") (name "Net-(IC1C-IN+)") (class "Default")
      (node (ref "IC1") (pin "10") (pinfunction "IN+_10") (pintype "input"))
      (node (ref "R109") (pin "2") (pinfunction "2_2") (pintype "passive"))
    )
    (net (code "84") (name "Net-(IC1C-IN-)") (class "Default")
      (node (ref "IC1") (pin "9") (pinfunction "IN-_9") (pintype "input"))
      (node (ref "R19") (pin "2") (pinfunction "2_2") (pintype "passive"))
      (node (ref "R92") (pin "1") (pinfunction "1_1") (pintype "passive"))
    )
    (net (code "85") (name "Net-(IC1D-IN+)") (class "Default")
      (node (ref "IC1") (pin "12") (pinfunction "IN+_12") (pintype "input"))
      (node (ref "R110") (pin "2") (pinfunction "2_2") (pintype "passive"))
    )
    (net (code "86") (name "Net-(IC1D-IN-)") (class "Default")
      (node (ref "IC1") (pin "13") (pinfunction "IN-_13") (pintype "input"))
      (node (ref "R20") (pin "2") (pinfunction "2_2") (pintype "passive"))
      (node (ref "R93") (pin "1") (pinfunction "1_1") (pintype "passive"))
    )
    (net (code "87") (name "Net-(IC2-AIN1)") (class "Default")
      (node (ref "C14") (pin "2") (pinfunction "2_2") (pintype "passive"))
      (node (ref "IC2") (pin "5") (pinfunction "AIN1_5") (pintype "input"))
      (node (ref "R49") (pin "2") (pinfunction "2_2") (pintype "passive"))
      (node (ref "R50") (pin "2") (pinfunction "2_2") (pintype "passive"))
    )
    (net (code "88") (name "Net-(IC2-AIN3)") (class "Default")
      (node (ref "C17") (pin "2") (pinfunction "2_2") (pintype "passive"))
      (node (ref "IC2") (pin "7") (pinfunction "AIN3_7") (pintype "input"))
      (node (ref "R31") (pin "2") (pinfunction "2_2") (pintype "passive"))
      (node (ref "R32") (pin "2") (pinfunction "2_2") (pintype "passive"))
    )
    (net (code "89") (name "Net-(IC4-A)") (class "Default")
      (node (ref "IC4") (pin "1") (pinfunction "A_1") (pintype "input"))
      (node (ref "R68") (pin "2") (pinfunction "2_2") (pintype "passive"))
    )
    (net (code "90") (name "Net-(IC6-ADJ)") (class "Default")
      (node (ref "IC6") (pin "1") (pinfunction "ADJ_1") (pintype "power_in"))
      (node (ref "R24") (pin "2") (pinfunction "2_2") (pintype "passive"))
      (node (ref "R25") (pin "1") (pinfunction "1_1") (pintype "passive"))
    )
    (net (code "91") (name "Net-(IC7-AIN0)") (class "Default")
      (node (ref "C10") (pin "2") (pinfunction "2_2") (pintype "passive"))
      (node (ref "IC7") (pin "4") (pinfunction "AIN0_4") (pintype "input"))
      (node (ref "R45") (pin "2") (pinfunction "2_2") (pintype "passive"))
    )
    (net (code "92") (name "Net-(IC7-AIN1)") (class "Default")
      (node (ref "C11") (pin "2") (pinfunction "2_2") (pintype "passive"))
      (node (ref "IC7") (pin "5") (pinfunction "AIN1_5") (pintype "input"))
      (node (ref "R46") (pin "2") (pinfunction "2_2") (pintype "passive"))
    )
    (net (code "93") (name "Net-(IC7-AIN2)") (class "Default")
      (node (ref "C12") (pin "2") (pinfunction "2_2") (pintype "passive"))
      (node (ref "IC7") (pin "6") (pinfunction "AIN2_6") (pintype "input"))
      (node (ref "R47") (pin "2") (pinfunction "2_2") (pintype "passive"))
    )
    (net (code "94") (name "Net-(IC7-AIN3)") (class "Default")
      (node (ref "C13") (pin "2") (pinfunction "2_2") (pintype "passive"))
      (node (ref "IC7") (pin "7") (pinfunction "AIN3_7") (pintype "input"))
      (node (ref "R48") (pin "2") (pinfunction "2_2") (pintype "passive"))
    )
    (net (code "95") (name "Net-(IC8A-IN-)") (class "Default")
      (node (ref "IC8") (pin "2") (pinfunction "IN-_2") (pintype "input"))
      (node (ref "R1") (pin "1") (pinfunction "1_1") (pintype "passive"))
      (node (ref "R2") (pin "2") (pinfunction "2_2") (pintype "passive"))
    )
    (net (code "96") (name "Net-(IC8B-IN-)") (class "Default")
      (node (ref "IC8") (pin "6") (pinfunction "IN-_6") (pintype "input"))
      (node (ref "R14") (pin "2") (pinfunction "2_2") (pintype "passive"))
      (node (ref "R6") (pin "1") (pinfunction "1_1") (pintype "passive"))
    )
    (net (code "97") (name "Net-(IC8C-IN-)") (class "Default")
      (node (ref "IC8") (pin "9") (pinfunction "IN-_9") (pintype "input"))
      (node (ref "R26") (pin "1") (pinfunction "1_1") (pintype "passive"))
      (node (ref "R52") (pin "2") (pinfunction "2_2") (pintype "passive"))
    )
    (net (code "98") (name "Net-(IC8D-IN-)") (class "Default")
      (node (ref "IC8") (pin "13") (pinfunction "IN-_13") (pintype "input"))
      (node (ref "R51") (pin "1") (pinfunction "1_1") (pintype "passive"))
      (node (ref "R60") (pin "2") (pinfunction "2_2") (pintype "passive"))
    )
    (net (code "99") (name "Net-(IC10-ADJ)") (class "Default")
      (node (ref "IC10") (pin "4") (pinfunction "ADJ_4") (pintype "passive"))
      (node (ref "R61") (pin "1") (pinfunction "1_1") (pintype "passive"))
      (node (ref "R63") (pin "2") (pinfunction "2_2") (pintype "passive"))
    )
    (net (code "100") (name "Net-(IC12-FB)") (class "Default")
      (node (ref "C25") (pin "1") (pinfunction "1_1") (pintype "passive"))
      (node (ref "IC12") (pin "3") (pinfunction "FB_3") (pintype "input"))
      (node (ref "R64") (pin "1") (pinfunction "1_1") (pintype "passive"))
      (node (ref "R66") (pin "2") (pinfunction "2_2") (pintype "passive"))
    )
    (net (code "101") (name "Net-(IC12-SHDN)") (class "Default")
      (node (ref "IC12") (pin "4") (pinfunction "SHDN_4") (pintype "input"))
      (node (ref "R65") (pin "1") (pinfunction "1_1") (pintype "passive"))
    )
    (net (code "102") (name "Net-(LD1-C)") (class "Default")
      (node (ref "LD1") (pin "1") (pinfunction "C_1") (pintype "passive"))
      (node (ref "R43") (pin "2") (pinfunction "2_2") (pintype "passive"))
    )
    (net (code "103") (name "Net-(LD2-C)") (class "Default")
      (node (ref "LD2") (pin "1") (pinfunction "C_1") (pintype "passive"))
      (node (ref "R44") (pin "2") (pinfunction "2_2") (pintype "passive"))
    )
    (net (code "104") (name "Net-(LD3-C)") (class "Default")
      (node (ref "LD3") (pin "1") (pinfunction "C_1") (pintype "passive"))
      (node (ref "R55") (pin "1") (pinfunction "1_1") (pintype "passive"))
    )
    (net (code "105") (name "Net-(R21-Pad2)") (class "Default")
      (node (ref "R21") (pin "2") (pinfunction "2_2") (pintype "passive"))
      (node (ref "R22") (pin "1") (pinfunction "1_1") (pintype "passive"))
    )
    (net (code "106") (name "Net-(R62-Pad2)") (class "Default")
      (node (ref "R62") (pin "2") (pinfunction "2_2") (pintype "passive"))
      (node (ref "R63") (pin "1") (pinfunction "1_1") (pintype "passive"))
    )
    (net (code "107") (name "Net-(T8-G)") (class "Default")
      (node (ref "R40") (pin "1") (pinfunction "1_1") (pintype "passive"))
      (node (ref "T8") (pin "1") (pinfunction "G_1") (pintype "passive"))
    )
    (net (code "108") (name "Net-(T9-G)") (class "Default")
      (node (ref "R42") (pin "1") (pinfunction "1_1") (pintype "passive"))
      (node (ref "T9") (pin "1") (pinfunction "G_1") (pintype "passive"))
    )
    (net (code "109") (name "Net-(T10A-B)") (class "Default")
      (node (ref "R34") (pin "2") (pinfunction "2_2") (pintype "passive"))
      (node (ref "T10") (pin "2") (pinfunction "B_2") (pintype "passive"))
    )
    (net (code "110") (name "Net-(T10B-B)") (class "Default")
      (node (ref "R35") (pin "2") (pinfunction "2_2") (pintype "passive"))
      (node (ref "T10") (pin "5") (pinfunction "B_5") (pintype "passive"))
    )
    (net (code "111") (name "Net-(T10B-C)") (class "Default")
      (node (ref "R38") (pin "1") (pinfunction "1_1") (pintype "passive"))
      (node (ref "T10") (pin "3") (pinfunction "C_3") (pintype "passive"))
    )
    (net (code "112") (name "Net-(U1-VDD)") (class "Default")
      (node (ref "C3") (pin "2") (pinfunction "2_2") (pintype "passive"))
      (node (ref "C7") (pin "2") (pinfunction "2_2") (pintype "passive"))
      (node (ref "R73") (pin "2") (pinfunction "2_2") (pintype "passive"))
      (node (ref "U1") (pin "1") (pinfunction "VDD_1") (pintype "power_in"))
    )
    (net (code "113") (name "P18V2") (class "Default")
      (node (ref "C19") (pin "2") (pinfunction "2_2") (pintype "passive"))
      (node (ref "C29") (pin "2") (pinfunction "2_2") (pintype "passive"))
      (node (ref "IC10") (pin "5") (pinfunction "OUT_5") (pintype "passive"))
      (node (ref "IC8") (pin "4") (pinfunction "V+_4") (pintype "power_in"))
      (node (ref "R61") (pin "2") (pinfunction "2_2") (pintype "passive"))
    )
    (net (code "114") (name "P36V0") (class "Default")
      (node (ref "C20") (pin "2") (pinfunction "2_2") (pintype "passive"))
      (node (ref "C25") (pin "2") (pinfunction "2_2") (pintype "passive"))
      (node (ref "C28") (pin "2") (pinfunction "2_2") (pintype "passive"))
      (node (ref "D7") (pin "1") (pinfunction "C_1") (pintype "passive"))
      (node (ref "D8") (pin "1") (pinfunction "C_1") (pintype "passive"))
      (node (ref "D9") (pin "1") (pinfunction "C_1") (pintype "passive"))
      (node (ref "IC10") (pin "1") (pinfunction "IN_1") (pintype "passive"))
      (node (ref "IC11") (pin "14") (pinfunction "V+_14") (pintype "power_in"))
      (node (ref "R64") (pin "2") (pinfunction "2_2") (pintype "passive"))
    )
    (net (code "115") (name "unconnected-(IC2-AIN2-Pad6)") (class "Default")
      (node (ref "IC2") (pin "6") (pinfunction "AIN2_6") (pintype "input+no_connect"))
    )
    (net (code "116") (name "unconnected-(IC2-ALERT-Pad2)") (class "Default")
      (node (ref "IC2") (pin "2") (pinfunction "ALERT_2") (pintype "output"))
    )
    (net (code "117") (name "unconnected-(IC4-Pad5)") (class "Default")
      (node (ref "IC4") (pin "5") (pinfunction "5_5") (pintype "passive"))
    )
    (net (code "118") (name "unconnected-(IC7-ALERT-Pad2)") (class "Default")
      (node (ref "IC7") (pin "2") (pinfunction "ALERT_2") (pintype "output"))
    )
    (net (code "119") (name "unconnected-(IC10-EN-Pad3)") (class "Default")
      (node (ref "IC10") (pin "3") (pinfunction "EN_3") (pintype "passive"))
    )
    (net (code "120") (name "unconnected-(IC11-NC-Pad8)") (class "Default")
      (node (ref "IC11") (pin "8") (pinfunction "NC_8") (pintype "passive"))
    )
    (net (code "121") (name "unconnected-(IC11-PA0-Pad13)") (class "Default")
      (node (ref "IC11") (pin "13") (pinfunction "PA0_13") (pintype "bidirectional"))
    )
    (net (code "122") (name "unconnected-(P1-Pad5)") (class "Default")
      (node (ref "P1") (pin "5") (pinfunction "5_5") (pintype "passive"))
    )
    (net (code "123") (name "unconnected-(P1-Pad6)") (class "Default")
      (node (ref "P1") (pin "6") (pinfunction "6_6") (pintype "passive"))
    )
    (net (code "124") (name "unconnected-(P1-Pad7)") (class "Default")
      (node (ref "P1") (pin "7") (pinfunction "7_7") (pintype "passive"))
    )
    (net (code "125") (name "unconnected-(P1-Pad9)") (class "Default")
      (node (ref "P1") (pin "9") (pinfunction "9_9") (pintype "passive"))
    )
    (net (code "126") (name "unconnected-(P1-Pad10)") (class "Default")
      (node (ref "P1") (pin "10") (pinfunction "10_10") (pintype "passive"))
    )
    (net (code "127") (name "unconnected-(P1-Pad11)") (class "Default")
      (node (ref "P1") (pin "11") (pinfunction "11_11") (pintype "passive"))
    )
    (net (code "128") (name "unconnected-(P1-Pad13)") (class "Default")
      (node (ref "P1") (pin "13") (pinfunction "13_13") (pintype "passive"))
    )
    (net (code "129") (name "unconnected-(P1-Pad14)") (class "Default")
      (node (ref "P1") (pin "14") (pinfunction "14_14") (pintype "passive"))
    )
    (net (code "130") (name "unconnected-(P1-Pad17)") (class "Default")
      (node (ref "P1") (pin "17") (pinfunction "17_17") (pintype "passive"))
    )
    (net (code "131") (name "unconnected-(P1-Pad18)") (class "Default")
      (node (ref "P1") (pin "18") (pinfunction "18_18") (pintype "passive"))
    )
    (net (code "132") (name "unconnected-(P1-Pad20)") (class "Default")
      (node (ref "P1") (pin "20") (pinfunction "20_20") (pintype "passive"))
    )
    (net (code "133") (name "unconnected-(P1-Pad21)") (class "Default")
      (node (ref "P1") (pin "21") (pinfunction "21_21") (pintype "passive"))
    )
    (net (code "134") (name "unconnected-(P1-Pad27)") (class "Default")
      (node (ref "P1") (pin "27") (pinfunction "27_27") (pintype "passive"))
    )
    (net (code "135") (name "unconnected-(P1-Pad28)") (class "Default")
      (node (ref "P1") (pin "28") (pinfunction "28_28") (pintype "passive"))
    )
    (net (code "136") (name "unconnected-(P1-Pad29)") (class "Default")
      (node (ref "P1") (pin "29") (pinfunction "29_29") (pintype "passive"))
    )
    (net (code "137") (name "unconnected-(P1-Pad30)") (class "Default")
      (node (ref "P1") (pin "30") (pinfunction "30_30") (pintype "passive"))
    )
    (net (code "138") (name "unconnected-(PCBM1-CLK-Pad20)") (class "Default")
      (node (ref "PCBM1") (pin "20") (pinfunction "CLK_20") (pintype "bidirectional"))
    )
    (net (code "139") (name "unconnected-(PCBM1-CMD-Pad19)") (class "Default")
      (node (ref "PCBM1") (pin "19") (pinfunction "CMD_19") (pintype "bidirectional"))
    )
    (net (code "140") (name "unconnected-(PCBM1-IO12-Pad14)") (class "Default")
      (node (ref "PCBM1") (pin "14") (pinfunction "IO12_14") (pintype "bidirectional"))
    )
    (net (code "141") (name "unconnected-(PCBM1-IO16-Pad27)") (class "Default")
      (node (ref "PCBM1") (pin "27") (pinfunction "IO16_27") (pintype "bidirectional"))
    )
    (net (code "142") (name "unconnected-(PCBM1-IO17-Pad28)") (class "Default")
      (node (ref "PCBM1") (pin "28") (pinfunction "IO17_28") (pintype "bidirectional"))
    )
    (net (code "143") (name "unconnected-(PCBM1-NC-Pad32)") (class "Default")
      (node (ref "PCBM1") (pin "32") (pinfunction "NC_32") (pintype "passive"))
    )
    (net (code "144") (name "unconnected-(PCBM1-SD0-Pad21)") (class "Default")
      (node (ref "PCBM1") (pin "21") (pinfunction "SD0_21") (pintype "bidirectional"))
    )
    (net (code "145") (name "unconnected-(PCBM1-SD1-Pad22)") (class "Default")
      (node (ref "PCBM1") (pin "22") (pinfunction "SD1_22") (pintype "bidirectional"))
    )
    (net (code "146") (name "unconnected-(PCBM1-SD2-Pad17)") (class "Default")
      (node (ref "PCBM1") (pin "17") (pinfunction "SD2_17") (pintype "bidirectional"))
    )
    (net (code "147") (name "unconnected-(PCBM1-SD3-Pad18)") (class "Default")
      (node (ref "PCBM1") (pin "18") (pinfunction "SD3_18") (pintype "bidirectional"))
    )
    (net (code "148") (name "unconnected-(PCBM1-SENSOR_VN-Pad5)") (class "Default")
      (node (ref "PCBM1") (pin "5") (pinfunction "SENSOR_VN_5") (pintype "input+no_connect"))
    )
    (net (code "149") (name "unconnected-(PCBM1-SENSOR_VP-Pad4)") (class "Default")
      (node (ref "PCBM1") (pin "4") (pinfunction "SENSOR_VP_4") (pintype "input+no_connect"))
    )
    (net (code "150") (name "unconnected-(U1-RDY{slash}~{BSY}-Pad5)") (class "Default")
      (node (ref "U1") (pin "5") (pinfunction "RDY/~{BSY}_5") (pintype "open_collector"))
    )
    (net (code "151") (name "unconnected-(U2-RDY{slash}~{BSY}-Pad5)") (class "Default")
      (node (ref "U2") (pin "5") (pinfunction "RDY/~{BSY}_5") (pintype "open_collector"))
    )
  )
)
